# PV_PWM_heater_v2.net
KiCad netlist of a schematic drawn in Altium Designer
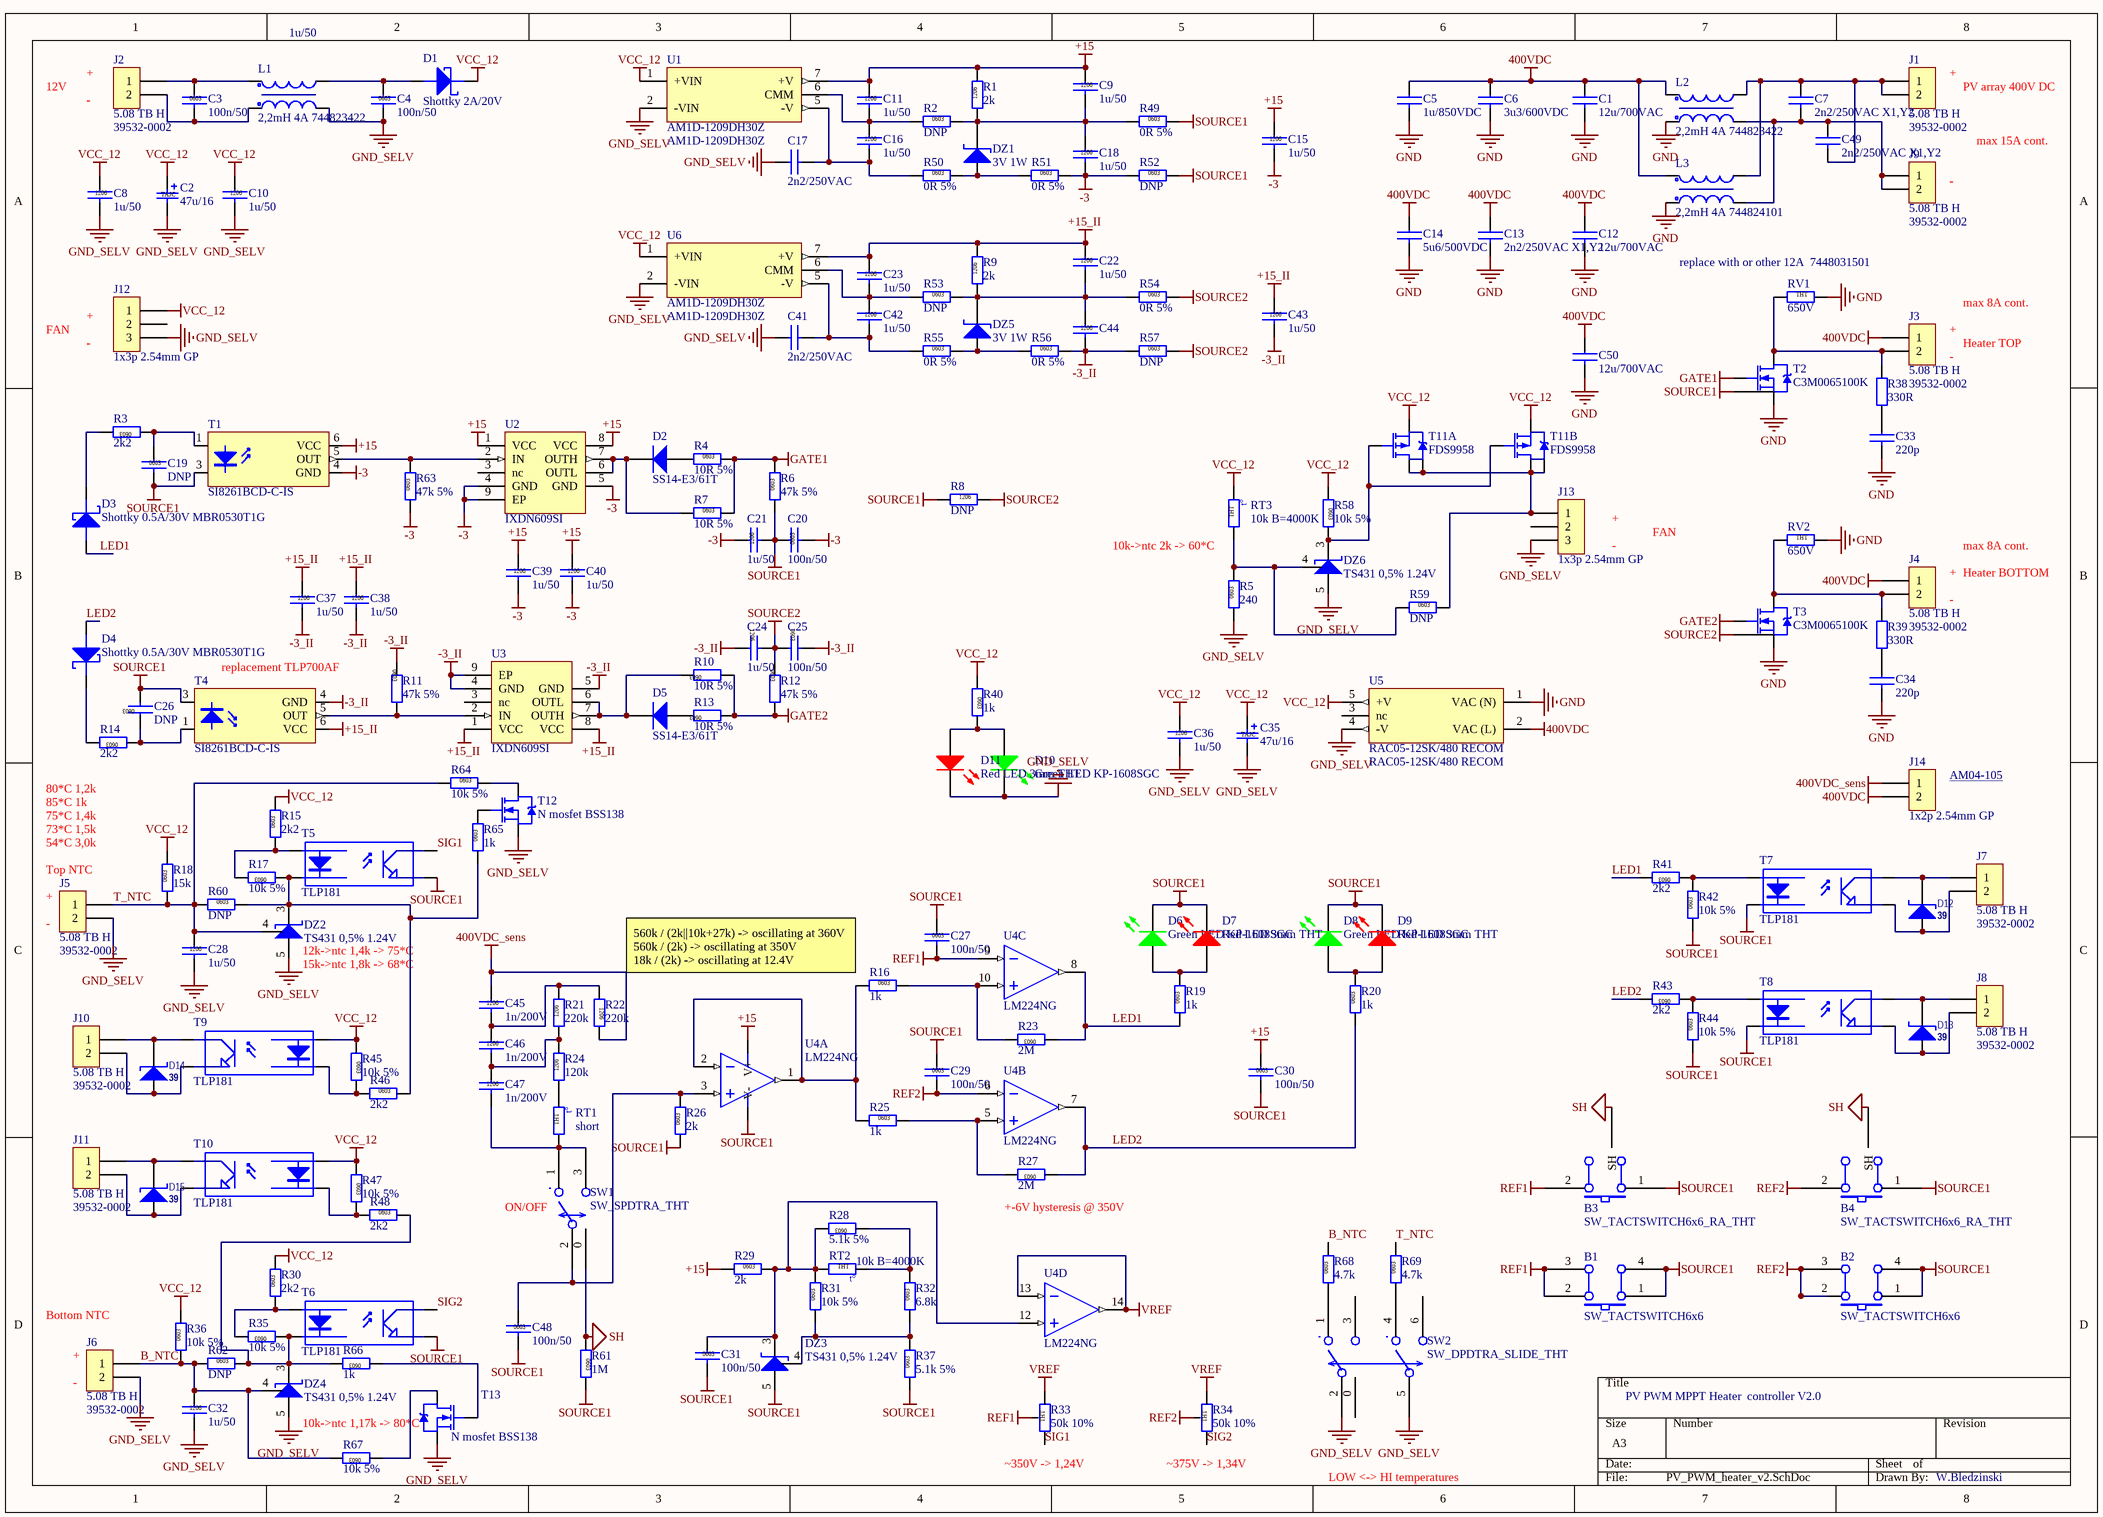
[diagram p0: PV_PWM_heater_v2.SchDoc]

(export (version "E")
  (design (tool "Eeschema 10.0.6"))
  (components
    (comp (ref "B1")
      (value "SW_TACTSWITCH6x6")
      (footprint "SW_TACT6x6")
      (description "SE PUSHBUTTON")
      (fields
        (field (name "MANUFACTURER") "ITT C&K")
        (field (name "MANUFACTURER PART NUMBER") "PTS645SK50SMTR92LFS")
      )
      (libsource (lib "WB") (part "SW_TACTSWITCH6x6"))
    )
    (comp (ref "B2")
      (value "SW_TACTSWITCH6x6")
      (footprint "SW_TACT6x6")
      (description "SE PUSHBUTTON")
      (fields
        (field (name "MANUFACTURER") "ITT C&K")
        (field (name "MANUFACTURER PART NUMBER") "PTS645SK50SMTR92LFS")
      )
      (libsource (lib "WB") (part "SW_TACTSWITCH6x6"))
    )
    (comp (ref "B3")
      (value "SW_TACTSWITCH6x6_RA_THT")
      (footprint "SW_TACT6x6_RA")
      (description "SE PUSHBUTTON")
      (fields (field (name "MANUFACTURER") "TE") (field (name "MANUFACTURER PART NUMBER") "1-1825027-1"))
      (libsource (lib "WB") (part "SW_TACTSWITCH6x6_RA_THT"))
    )
    (comp (ref "B4")
      (value "SW_TACTSWITCH6x6_RA_THT")
      (footprint "SW_TACT6x6_RA")
      (description "SE PUSHBUTTON")
      (fields (field (name "MANUFACTURER") "TE") (field (name "MANUFACTURER PART NUMBER") "1-1825027-1"))
      (libsource (lib "WB") (part "SW_TACTSWITCH6x6_RA_THT"))
    )
    (comp (ref "C1")
      (value "12u/700VAC")
      (footprint "CAP_THT27.5mm")
      (description "poliester capacitor THT")
      (fields
        (field (name "MANUFACTURER") "EPCOS")
        (field (name "MANUFACTURER PART NUMBER") "B32774D8126K000")
      )
      (libsource (lib "WB") (part "CAP_B_12u_700_THT"))
    )
    (comp (ref "C2")
      (value "47u/16")
      (footprint "TAJC")
      (description "ESR 1.2R 10VDC at 125stC")
      (fields
        (field (name "MANUFACTURER") "KEMET")
        (field (name "MANUFACTURER PART NUMBER") "T491C476K016AT")
      )
      (libsource (lib "WB") (part "CAP_E_47u_16_TAJC"))
    )
    (comp (ref "C3")
      (value "100n/50")
      (footprint "CAP_0603")
      (description "X7R chip capacitor")
      (fields
        (field (name "MANUFACTURER") "SAMSUNG")
        (field (name "MANUFACTURER PART NUMBER") "CL10B104KB8NNNC")
      )
      (libsource (lib "WB") (part "CAP_B_100n_50_0603_X7R"))
    )
    (comp (ref "C4")
      (value "100n/50")
      (footprint "CAP_0603")
      (description "X7R chip capacitor")
      (fields
        (field (name "MANUFACTURER") "SAMSUNG")
        (field (name "MANUFACTURER PART NUMBER") "CL10B104KB8NNNC")
      )
      (libsource (lib "WB") (part "CAP_B_100n_50_0603_X7R"))
    )
    (comp (ref "C5")
      (value "1u/850VDC")
      (footprint "CAP_AXIAL50X20mm")
      (description "poliester capacitor THT, esr 5mR, 9A/140A pk")
      (fields
        (field (name "MANUFACTURER") "KEMET")
        (field (name "MANUFACTURER PART NUMBER") "C4GAMUC4100AA1J")
      )
      (libsource (lib "WB") (part "CAP_B_1u_850_THT"))
    )
    (comp (ref "C6")
      (value "3u3/600VDC")
      (footprint "CAP_THT27.5X22mm")
      (description "poliester capacitor THT, esr 2.4mR, 25A/342A pk; 350VAC")
      (fields
        (field (name "MANUFACTURER") "KEMET")
        (field (name "MANUFACTURER PART NUMBER") "C4ATHBW4330A3GJ")
      )
      (libsource (lib "WB") (part "CAP_B_3u3_600_THT"))
    )
    (comp (ref "C7")
      (value "2n2/250VAC X1,Y2")
      (footprint "CAP_THT7.5mm")
      (description "poliester capacitor THT X1 Y2, Y5V")
      (fields (field (name "MANUFACTURER PART NUMBER") "CY2V-2N2") (field (name "TOLERANCE") "20%"))
      (libsource (lib "WB") (part "CAP_B_2n2_250_X1Y2_THT"))
    )
    (comp (ref "C8")
      (value "1u/50")
      (footprint "CAP_1206")
      (description "X7R chip capacitor")
      (fields
        (field (name "MANUFACTURER") "TDK")
        (field (name "MANUFACTURER PART NUMBER") "C3216X7R1H105K160AB")
      )
      (libsource (lib "WB") (part "CAP_B_1u_50_1206_X7R"))
    )
    (comp (ref "C9")
      (value "1u/50")
      (footprint "CAP_1206")
      (description "X7R chip capacitor")
      (fields
        (field (name "MANUFACTURER") "TDK")
        (field (name "MANUFACTURER PART NUMBER") "C3216X7R1H105K160AB")
      )
      (libsource (lib "WB") (part "CAP_B_1u_50_1206_X7R"))
    )
    (comp (ref "C10")
      (value "1u/50")
      (footprint "CAP_1206")
      (description "X7R chip capacitor")
      (fields
        (field (name "MANUFACTURER") "TDK")
        (field (name "MANUFACTURER PART NUMBER") "C3216X7R1H105K160AB")
      )
      (libsource (lib "WB") (part "CAP_B_1u_50_1206_X7R"))
    )
    (comp (ref "C11")
      (value "1u/50")
      (footprint "CAP_1206")
      (description "X7R chip capacitor")
      (fields
        (field (name "MANUFACTURER") "TDK")
        (field (name "MANUFACTURER PART NUMBER") "C3216X7R1H105K160AB")
      )
      (libsource (lib "WB") (part "CAP_B_1u_50_1206_X7R"))
    )
    (comp (ref "C12")
      (value "12u/700VAC")
      (footprint "CAP_THT27.5mm")
      (description "poliester capacitor THT")
      (fields
        (field (name "MANUFACTURER") "EPCOS")
        (field (name "MANUFACTURER PART NUMBER") "B32774D8126K000")
      )
      (libsource (lib "WB") (part "CAP_B_12u_700_THT"))
    )
    (comp (ref "C13")
      (value "2n2/250VAC X1,Y2")
      (footprint "CAP_THT7.5mm")
      (description "poliester capacitor THT X1 Y2, Y5V")
      (fields (field (name "MANUFACTURER PART NUMBER") "CY2V-2N2") (field (name "TOLERANCE") "20%"))
      (libsource (lib "WB") (part "CAP_B_2n2_250_X1Y2_THT"))
    )
    (comp (ref "C14")
      (value "5u6/500VDC")
      (footprint "CAP_THT27.5X11mm")
      (description "poliester capacitor THT, esr 13mR,")
      (fields (field (name "TOLERANCE") "10%") (field (name "VOLTAGE") "500VDC"))
      (libsource (lib "WB") (part "CAP_B_5u6_500_THT"))
    )
    (comp (ref "C15")
      (value "1u/50")
      (footprint "CAP_1206")
      (description "X7R chip capacitor")
      (fields
        (field (name "MANUFACTURER") "TDK")
        (field (name "MANUFACTURER PART NUMBER") "C3216X7R1H105K160AB")
      )
      (libsource (lib "WB") (part "CAP_B_1u_50_1206_X7R"))
    )
    (comp (ref "C16")
      (value "1u/50")
      (footprint "CAP_1206")
      (description "X7R chip capacitor")
      (fields
        (field (name "MANUFACTURER") "TDK")
        (field (name "MANUFACTURER PART NUMBER") "C3216X7R1H105K160AB")
      )
      (libsource (lib "WB") (part "CAP_B_1u_50_1206_X7R"))
    )
    (comp (ref "C17")
      (value "2n2/250VAC")
      (footprint "CAP_THT10mm")
      (description "poliester capacitor THT Y2")
      (fields
        (field (name "MANUFACTURER") "WIMA")
        (field (name "MANUFACTURER PART NUMBER") "MPY20W1220FA00MSSD")
      )
      (libsource (lib "WB") (part "CAP_B_2n2_250_THT"))
    )
    (comp (ref "C18")
      (value "1u/50")
      (footprint "CAP_1206")
      (description "X7R chip capacitor")
      (fields
        (field (name "MANUFACTURER") "TDK")
        (field (name "MANUFACTURER PART NUMBER") "C3216X7R1H105K160AB")
      )
      (libsource (lib "WB") (part "CAP_B_1u_50_1206_X7R"))
    )
    (comp (ref "C19")
      (value "DNP")
      (footprint "CAP_0603")
      (description "X7R chip capacitor")
      (fields
        (field (name "MANUFACTURER") "SAMSUNG")
        (field (name "MANUFACTURER PART NUMBER") "CL10B104KB8NNNC")
      )
      (libsource (lib "WB") (part "CAP_B_100n_50_0603_X7R"))
    )
    (comp (ref "C20")
      (value "100n/50")
      (footprint "CAP_0603")
      (description "X7R chip capacitor")
      (fields
        (field (name "MANUFACTURER") "SAMSUNG")
        (field (name "MANUFACTURER PART NUMBER") "CL10B104KB8NNNC")
      )
      (libsource (lib "WB") (part "CAP_B_100n_50_0603_X7R"))
    )
    (comp (ref "C21")
      (value "1u/50")
      (footprint "CAP_1206")
      (description "X7R chip capacitor")
      (fields
        (field (name "MANUFACTURER") "TDK")
        (field (name "MANUFACTURER PART NUMBER") "C3216X7R1H105K160AB")
      )
      (libsource (lib "WB") (part "CAP_B_1u_50_1206_X7R"))
    )
    (comp (ref "C22")
      (value "1u/50")
      (footprint "CAP_1206")
      (description "X7R chip capacitor")
      (fields
        (field (name "MANUFACTURER") "TDK")
        (field (name "MANUFACTURER PART NUMBER") "C3216X7R1H105K160AB")
      )
      (libsource (lib "WB") (part "CAP_B_1u_50_1206_X7R"))
    )
    (comp (ref "C23")
      (value "1u/50")
      (footprint "CAP_1206")
      (description "X7R chip capacitor")
      (fields
        (field (name "MANUFACTURER") "TDK")
        (field (name "MANUFACTURER PART NUMBER") "C3216X7R1H105K160AB")
      )
      (libsource (lib "WB") (part "CAP_B_1u_50_1206_X7R"))
    )
    (comp (ref "C24")
      (value "1u/50")
      (footprint "CAP_1206")
      (description "X7R chip capacitor")
      (fields
        (field (name "MANUFACTURER") "TDK")
        (field (name "MANUFACTURER PART NUMBER") "C3216X7R1H105K160AB")
      )
      (libsource (lib "WB") (part "CAP_B_1u_50_1206_X7R"))
    )
    (comp (ref "C25")
      (value "100n/50")
      (footprint "CAP_0603")
      (description "X7R chip capacitor")
      (fields
        (field (name "MANUFACTURER") "SAMSUNG")
        (field (name "MANUFACTURER PART NUMBER") "CL10B104KB8NNNC")
      )
      (libsource (lib "WB") (part "CAP_B_100n_50_0603_X7R"))
    )
    (comp (ref "C26")
      (value "DNP")
      (footprint "CAP_0603")
      (description "X7R chip capacitor")
      (fields
        (field (name "MANUFACTURER") "SAMSUNG")
        (field (name "MANUFACTURER PART NUMBER") "CL10B104KB8NNNC")
      )
      (libsource (lib "WB") (part "CAP_B_100n_50_0603_X7R"))
    )
    (comp (ref "C27")
      (value "100n/50")
      (footprint "CAP_0603")
      (description "X7R chip capacitor")
      (fields
        (field (name "MANUFACTURER") "SAMSUNG")
        (field (name "MANUFACTURER PART NUMBER") "CL10B104KB8NNNC")
      )
      (libsource (lib "WB") (part "CAP_B_100n_50_0603_X7R"))
    )
    (comp (ref "C28")
      (value "1u/50")
      (footprint "CAP_1206")
      (description "X7R chip capacitor")
      (fields
        (field (name "MANUFACTURER") "TDK")
        (field (name "MANUFACTURER PART NUMBER") "C3216X7R1H105K160AB")
      )
      (libsource (lib "WB") (part "CAP_B_1u_50_1206_X7R"))
    )
    (comp (ref "C29")
      (value "100n/50")
      (footprint "CAP_0603")
      (description "X7R chip capacitor")
      (fields
        (field (name "MANUFACTURER") "SAMSUNG")
        (field (name "MANUFACTURER PART NUMBER") "CL10B104KB8NNNC")
      )
      (libsource (lib "WB") (part "CAP_B_100n_50_0603_X7R"))
    )
    (comp (ref "C30")
      (value "100n/50")
      (footprint "CAP_0603")
      (description "X7R chip capacitor")
      (fields
        (field (name "MANUFACTURER") "SAMSUNG")
        (field (name "MANUFACTURER PART NUMBER") "CL10B104KB8NNNC")
      )
      (libsource (lib "WB") (part "CAP_B_100n_50_0603_X7R"))
    )
    (comp (ref "C31")
      (value "100n/50")
      (footprint "CAP_0603")
      (description "X7R chip capacitor")
      (fields
        (field (name "MANUFACTURER") "SAMSUNG")
        (field (name "MANUFACTURER PART NUMBER") "CL10B104KB8NNNC")
      )
      (libsource (lib "WB") (part "CAP_B_100n_50_0603_X7R"))
    )
    (comp (ref "C32")
      (value "1u/50")
      (footprint "CAP_1206")
      (description "X7R chip capacitor")
      (fields
        (field (name "MANUFACTURER") "TDK")
        (field (name "MANUFACTURER PART NUMBER") "C3216X7R1H105K160AB")
      )
      (libsource (lib "WB") (part "CAP_B_1u_50_1206_X7R"))
    )
    (comp (ref "C33")
      (value "220p")
      (footprint "CAP_THT7.5mm")
      (description "poliester capacitor THT X1 Y2, Y5V")
      (fields (field (name "MANUFACTURER PART NUMBER") "CY2V-2N2") (field (name "TOLERANCE") "20%"))
      (libsource (lib "WB") (part "CAP_B_2n2_250_X1Y2_THT"))
    )
    (comp (ref "C34")
      (value "220p")
      (footprint "CAP_THT7.5mm")
      (description "poliester capacitor THT X1 Y2, Y5V")
      (fields (field (name "MANUFACTURER PART NUMBER") "CY2V-2N2") (field (name "TOLERANCE") "20%"))
      (libsource (lib "WB") (part "CAP_B_2n2_250_X1Y2_THT"))
    )
    (comp (ref "C35")
      (value "47u/16")
      (footprint "TAJC")
      (description "ESR 1.2R 10VDC at 125stC")
      (fields
        (field (name "MANUFACTURER") "KEMET")
        (field (name "MANUFACTURER PART NUMBER") "T491C476K016AT")
      )
      (libsource (lib "WB") (part "CAP_E_47u_16_TAJC"))
    )
    (comp (ref "C36")
      (value "1u/50")
      (footprint "CAP_1206")
      (description "X7R chip capacitor")
      (fields
        (field (name "MANUFACTURER") "TDK")
        (field (name "MANUFACTURER PART NUMBER") "C3216X7R1H105K160AB")
      )
      (libsource (lib "WB") (part "CAP_B_1u_50_1206_X7R"))
    )
    (comp (ref "C37")
      (value "1u/50")
      (footprint "CAP_1206")
      (description "X7R chip capacitor")
      (fields
        (field (name "MANUFACTURER") "TDK")
        (field (name "MANUFACTURER PART NUMBER") "C3216X7R1H105K160AB")
      )
      (libsource (lib "WB") (part "CAP_B_1u_50_1206_X7R"))
    )
    (comp (ref "C38")
      (value "1u/50")
      (footprint "CAP_1206")
      (description "X7R chip capacitor")
      (fields
        (field (name "MANUFACTURER") "TDK")
        (field (name "MANUFACTURER PART NUMBER") "C3216X7R1H105K160AB")
      )
      (libsource (lib "WB") (part "CAP_B_1u_50_1206_X7R"))
    )
    (comp (ref "C39")
      (value "1u/50")
      (footprint "CAP_1206")
      (description "X7R chip capacitor")
      (fields
        (field (name "MANUFACTURER") "TDK")
        (field (name "MANUFACTURER PART NUMBER") "C3216X7R1H105K160AB")
      )
      (libsource (lib "WB") (part "CAP_B_1u_50_1206_X7R"))
    )
    (comp (ref "C40")
      (value "1u/50")
      (footprint "CAP_1206")
      (description "X7R chip capacitor")
      (fields
        (field (name "MANUFACTURER") "TDK")
        (field (name "MANUFACTURER PART NUMBER") "C3216X7R1H105K160AB")
      )
      (libsource (lib "WB") (part "CAP_B_1u_50_1206_X7R"))
    )
    (comp (ref "C41")
      (value "2n2/250VAC")
      (footprint "CAP_THT10mm")
      (description "poliester capacitor THT Y2")
      (fields
        (field (name "MANUFACTURER") "WIMA")
        (field (name "MANUFACTURER PART NUMBER") "MPY20W1220FA00MSSD")
      )
      (libsource (lib "WB") (part "CAP_B_2n2_250_THT"))
    )
    (comp (ref "C42")
      (value "1u/50")
      (footprint "CAP_1206")
      (description "X7R chip capacitor")
      (fields
        (field (name "MANUFACTURER") "TDK")
        (field (name "MANUFACTURER PART NUMBER") "C3216X7R1H105K160AB")
      )
      (libsource (lib "WB") (part "CAP_B_1u_50_1206_X7R"))
    )
    (comp (ref "C43")
      (value "1u/50")
      (footprint "CAP_1206")
      (description "X7R chip capacitor")
      (fields
        (field (name "MANUFACTURER") "TDK")
        (field (name "MANUFACTURER PART NUMBER") "C3216X7R1H105K160AB")
      )
      (libsource (lib "WB") (part "CAP_B_1u_50_1206_X7R"))
    )
    (comp (ref "C44")
      (value "1u/50")
      (footprint "CAP_1206")
      (description "X7R chip capacitor")
      (fields
        (field (name "MANUFACTURER") "TDK")
        (field (name "MANUFACTURER PART NUMBER") "C3216X7R1H105K160AB")
      )
      (libsource (lib "WB") (part "CAP_B_1u_50_1206_X7R"))
    )
    (comp (ref "C45")
      (value "1n/200V")
      (footprint "CAP_1206")
      (description "C0G chip capacitor")
      (fields
        (field (name "MANUFACTURER") "TDK")
        (field (name "MANUFACTURER PART NUMBER") "CGA5L2C0G1H104J160AA")
      )
      (libsource (lib "WB") (part "CAP_B_100n_50_1206_C0G"))
    )
    (comp (ref "C46")
      (value "1n/200V")
      (footprint "CAP_1206")
      (description "C0G chip capacitor")
      (fields
        (field (name "MANUFACTURER") "TDK")
        (field (name "MANUFACTURER PART NUMBER") "CGA5L2C0G1H104J160AA")
      )
      (libsource (lib "WB") (part "CAP_B_100n_50_1206_C0G"))
    )
    (comp (ref "C47")
      (value "1n/200V")
      (footprint "CAP_1206")
      (description "C0G chip capacitor")
      (fields
        (field (name "MANUFACTURER") "TDK")
        (field (name "MANUFACTURER PART NUMBER") "CGA5L2C0G1H104J160AA")
      )
      (libsource (lib "WB") (part "CAP_B_100n_50_1206_C0G"))
    )
    (comp (ref "C48")
      (value "100n/50")
      (footprint "CAP_0603")
      (description "X7R chip capacitor")
      (fields
        (field (name "MANUFACTURER") "SAMSUNG")
        (field (name "MANUFACTURER PART NUMBER") "CL10B104KB8NNNC")
      )
      (libsource (lib "WB") (part "CAP_B_100n_50_0603_X7R"))
    )
    (comp (ref "C49")
      (value "2n2/250VAC X1,Y2")
      (footprint "CAP_THT7.5mm")
      (description "poliester capacitor THT X1 Y2, Y5V")
      (fields (field (name "MANUFACTURER PART NUMBER") "CY2V-2N2") (field (name "TOLERANCE") "20%"))
      (libsource (lib "WB") (part "CAP_B_2n2_250_X1Y2_THT"))
    )
    (comp (ref "C50")
      (value "12u/700VAC")
      (footprint "CAP_THT27.5mm")
      (description "poliester capacitor THT")
      (fields
        (field (name "MANUFACTURER") "EPCOS")
        (field (name "MANUFACTURER PART NUMBER") "B32774D8126K000")
      )
      (libsource (lib "WB") (part "CAP_B_12u_700_THT"))
    )
    (comp (ref "D1")
      (value "Shottky 2A/20V")
      (footprint "SMA_DO-214AC")
      (description "Shottky Diode 0,5V @ 2A SMA 200pF")
      (fields (field (name "MANUFACTURER") "DIODES") (field (name "MANUFACTURER PART NUMBER") "B220A-13-F"))
      (libsource (lib "WB") (part "D_2A_20_B220A"))
    )
    (comp (ref "D2")
      (value "SS14-E3/61T")
      (footprint "SMA_DO-214AC")
      (fields (field (name "MANUFACTURER") "Vishay Semiconductors"))
      (libsource (lib "WB") (part "D_SS14"))
    )
    (comp (ref "D3")
      (value "Shottky 0.5A/30V MBR0530T1G")
      (footprint "SOD_123")
      (description "Shottky Diode trr 4ns 0,43V @ 0.5A 0.37V@0.1A")
      (fields (field (name "MANUFACTURER") "ON") (field (name "MANUFACTURER PART NUMBER") "MBR0530T1G"))
      (libsource (lib "WB") (part "D_0.5A_30_MBR0530T1G"))
    )
    (comp (ref "D4")
      (value "Shottky 0.5A/30V MBR0530T1G")
      (footprint "SOD_123")
      (description "Shottky Diode trr 4ns 0,43V @ 0.5A 0.37V@0.1A")
      (fields (field (name "MANUFACTURER") "ON") (field (name "MANUFACTURER PART NUMBER") "MBR0530T1G"))
      (libsource (lib "WB") (part "D_0.5A_30_MBR0530T1G"))
    )
    (comp (ref "D5")
      (value "SS14-E3/61T")
      (footprint "SMA_DO-214AC")
      (fields (field (name "MANUFACTURER") "Vishay Semiconductors"))
      (libsource (lib "WB") (part "D_SS14"))
    )
    (comp (ref "D6")
      (value "Green LED KP-1608SGC")
      (footprint "LED_0603_GREEN")
      (description "Diode LED SMD 2.2V @ 20mA 15mcd")
      (fields
        (field (name "MANUFACTURER") "KINGBRIGHT")
        (field (name "MANUFACTURER PART NUMBER") "KP-1608SGC")
      )
      (libsource (lib "WB") (part "D_LED_0603_GREEN"))
    )
    (comp (ref "D7")
      (value "Red LED 3mm THT")
      (footprint "LED_3MM")
      (description "Diode LED THT")
      (fields
        (field (name "MANUFACTURER") "KINGBRIGHT")
        (field (name "MANUFACTURER PART NUMBER") "L-934SRC-E")
      )
      (libsource (lib "WB") (part "D_LED3_THT_RED"))
    )
    (comp (ref "D8")
      (value "Green LED KP-1608SGC")
      (footprint "LED_0603_GREEN")
      (description "Diode LED SMD 2.2V @ 20mA 15mcd")
      (fields
        (field (name "MANUFACTURER") "KINGBRIGHT")
        (field (name "MANUFACTURER PART NUMBER") "KP-1608SGC")
      )
      (libsource (lib "WB") (part "D_LED_0603_GREEN"))
    )
    (comp (ref "D9")
      (value "Red LED 3mm THT")
      (footprint "LED_3MM")
      (description "Diode LED THT")
      (fields
        (field (name "MANUFACTURER") "KINGBRIGHT")
        (field (name "MANUFACTURER PART NUMBER") "L-934SRC-E")
      )
      (libsource (lib "WB") (part "D_LED3_THT_RED"))
    )
    (comp (ref "D10")
      (value "Green LED KP-1608SGC")
      (footprint "LED_0603_GREEN")
      (description "Diode LED SMD 2.2V @ 20mA 15mcd")
      (fields
        (field (name "MANUFACTURER") "KINGBRIGHT")
        (field (name "MANUFACTURER PART NUMBER") "KP-1608SGC")
      )
      (libsource (lib "WB") (part "D_LED_0603_GREEN"))
    )
    (comp (ref "D11")
      (value "Red LED 3mm THT")
      (footprint "LED_3MM")
      (description "Diode LED THT")
      (fields
        (field (name "MANUFACTURER") "KINGBRIGHT")
        (field (name "MANUFACTURER PART NUMBER") "L-934SRC-E")
      )
      (libsource (lib "WB") (part "D_LED3_THT_RED"))
    )
    (comp (ref "D12")
      (value "39")
      (footprint "SMA_DO-214AC")
      (description "transil jednostronny")
      (fields (field (name "MANUFACTURER") "STM") (field (name "MANUFACTURER PART NUMBER") "SMA6T39AY"))
      (libsource (lib "WB") (part "D_TR_UNI_SMA6TY_39V"))
    )
    (comp (ref "D13")
      (value "39")
      (footprint "SMA_DO-214AC")
      (description "transil jednostronny")
      (fields (field (name "MANUFACTURER") "STM") (field (name "MANUFACTURER PART NUMBER") "SMA6T39AY"))
      (libsource (lib "WB") (part "D_TR_UNI_SMA6TY_39V"))
    )
    (comp (ref "D14")
      (value "39")
      (footprint "SMA_DO-214AC")
      (description "transil jednostronny")
      (fields (field (name "MANUFACTURER") "STM") (field (name "MANUFACTURER PART NUMBER") "SMA6T39AY"))
      (libsource (lib "WB") (part "D_TR_UNI_SMA6TY_39V"))
    )
    (comp (ref "D15")
      (value "39")
      (footprint "SMA_DO-214AC")
      (description "transil jednostronny")
      (fields (field (name "MANUFACTURER") "STM") (field (name "MANUFACTURER PART NUMBER") "SMA6T39AY"))
      (libsource (lib "WB") (part "D_TR_UNI_SMA6TY_39V"))
    )
    (comp (ref "DZ1")
      (value "3V 1W")
      (footprint "D_DO-15_DO-204AC")
      (fields (field (name "VOLTAGE") "3"))
      (libsource (lib "WB") (part "D_1W_20_ZENER"))
    )
    (comp (ref "DZ2")
      (value "TS431 0,5% 1.24V")
      (footprint "SOT23_5_DBV_R-PDSO-G5")
      (description "0,5% 1.24V vref")
      (fields (field (name "VOLTAGE") "10V") (field (name "MANUFACTURER") "STMicroelectronics"))
      (libsource (lib "WB") (part "D_TS431BILT"))
    )
    (comp (ref "DZ3")
      (value "TS431 0,5% 1.24V")
      (footprint "SOT23_5_DBV_R-PDSO-G5")
      (description "0,5% 1.24V vref")
      (fields (field (name "VOLTAGE") "10V") (field (name "MANUFACTURER") "STMicroelectronics"))
      (libsource (lib "WB") (part "D_TS431BILT"))
    )
    (comp (ref "DZ4")
      (value "TS431 0,5% 1.24V")
      (footprint "SOT23_5_DBV_R-PDSO-G5")
      (description "0,5% 1.24V vref")
      (fields (field (name "VOLTAGE") "10V") (field (name "MANUFACTURER") "STMicroelectronics"))
      (libsource (lib "WB") (part "D_TS431BILT"))
    )
    (comp (ref "DZ5")
      (value "3V 1W")
      (footprint "D_DO-15_DO-204AC")
      (fields (field (name "VOLTAGE") "3"))
      (libsource (lib "WB") (part "D_1W_20_ZENER"))
    )
    (comp (ref "DZ6")
      (value "TS431 0,5% 1.24V")
      (footprint "SOT23_5_DBV_R-PDSO-G5")
      (description "0,5% 1.24V vref")
      (fields (field (name "VOLTAGE") "10V") (field (name "MANUFACTURER") "STMicroelectronics"))
      (libsource (lib "WB") (part "D_TS431BILT"))
    )
    (comp (ref "J1")
      (value "5.08 TB H")
      (footprint "CON_1x2_5.08TBRA")
      (description "THT 5,08mm, WE 691312510002, NINIGI TBG-5-KB-2P/GN, MLX 395320002")
      (fields (field (name "MANUFACTURER") "Molex") (field (name "MANUFACTURER PART NUMBER") "39532-0002"))
      (libsource (lib "") (part "CON_1x2_TB_5.08H_1"))
    )
    (comp (ref "J2")
      (value "5.08 TB H")
      (footprint "CON_1x2_5.08TBRA")
      (description "THT 5,08mm, WE 691312510002, NINIGI TBG-5-KB-2P/GN, MLX 395320002")
      (fields (field (name "MANUFACTURER") "Molex") (field (name "MANUFACTURER PART NUMBER") "39532-0002"))
      (libsource (lib "WB") (part "CON_1x2_TB_5.08H"))
    )
    (comp (ref "J3")
      (value "5.08 TB H")
      (footprint "CON_1x2_5.08TBRA")
      (description "THT 5,08mm, WE 691312510002, NINIGI TBG-5-KB-2P/GN, MLX 395320002")
      (fields (field (name "MANUFACTURER") "Molex") (field (name "MANUFACTURER PART NUMBER") "39532-0002"))
      (libsource (lib "") (part "CON_1x2_TB_5.08H_1"))
    )
    (comp (ref "J4")
      (value "5.08 TB H")
      (footprint "CON_1x2_5.08TBRA")
      (description "THT 5,08mm, WE 691312510002, NINIGI TBG-5-KB-2P/GN, MLX 395320002")
      (fields (field (name "MANUFACTURER") "Molex") (field (name "MANUFACTURER PART NUMBER") "39532-0002"))
      (libsource (lib "") (part "CON_1x2_TB_5.08H_1"))
    )
    (comp (ref "J5")
      (value "5.08 TB H")
      (footprint "CON_1x2_5.08TBRA")
      (description "THT 5,08mm, WE 691312510002, NINIGI TBG-5-KB-2P/GN, MLX 395320002")
      (fields (field (name "MANUFACTURER") "Molex") (field (name "MANUFACTURER PART NUMBER") "39532-0002"))
      (libsource (lib "WB") (part "CON_1x2_TB_5.08H"))
    )
    (comp (ref "J6")
      (value "5.08 TB H")
      (footprint "CON_1x2_5.08TBRA")
      (description "THT 5,08mm, WE 691312510002, NINIGI TBG-5-KB-2P/GN, MLX 395320002")
      (fields (field (name "MANUFACTURER") "Molex") (field (name "MANUFACTURER PART NUMBER") "39532-0002"))
      (libsource (lib "WB") (part "CON_1x2_TB_5.08H"))
    )
    (comp (ref "J7")
      (value "5.08 TB H")
      (footprint "CON_1x2_5.08TBRA")
      (description "THT 5,08mm, WE 691312510002, NINIGI TBG-5-KB-2P/GN, MLX 395320002")
      (fields (field (name "MANUFACTURER") "Molex") (field (name "MANUFACTURER PART NUMBER") "39532-0002"))
      (libsource (lib "") (part "CON_1x2_TB_5.08H_1"))
    )
    (comp (ref "J8")
      (value "5.08 TB H")
      (footprint "CON_1x2_5.08TBRA")
      (description "THT 5,08mm, WE 691312510002, NINIGI TBG-5-KB-2P/GN, MLX 395320002")
      (fields (field (name "MANUFACTURER") "Molex") (field (name "MANUFACTURER PART NUMBER") "39532-0002"))
      (libsource (lib "") (part "CON_1x2_TB_5.08H_1"))
    )
    (comp (ref "J9")
      (value "5.08 TB H")
      (footprint "CON_1x2_5.08TBRA")
      (description "THT 5,08mm, WE 691312510002, NINIGI TBG-5-KB-2P/GN, MLX 395320002")
      (fields (field (name "MANUFACTURER") "Molex") (field (name "MANUFACTURER PART NUMBER") "39532-0002"))
      (libsource (lib "") (part "CON_1x2_TB_5.08H_1"))
    )
    (comp (ref "J10")
      (value "5.08 TB H")
      (footprint "CON_1x2_5.08TBRA")
      (description "THT 5,08mm, WE 691312510002, NINIGI TBG-5-KB-2P/GN, MLX 395320002")
      (fields (field (name "MANUFACTURER") "Molex") (field (name "MANUFACTURER PART NUMBER") "39532-0002"))
      (libsource (lib "WB") (part "CON_1x2_TB_5.08H"))
    )
    (comp (ref "J11")
      (value "5.08 TB H")
      (footprint "CON_1x2_5.08TBRA")
      (description "THT 5,08mm, WE 691312510002, NINIGI TBG-5-KB-2P/GN, MLX 395320002")
      (fields (field (name "MANUFACTURER") "Molex") (field (name "MANUFACTURER PART NUMBER") "39532-0002"))
      (libsource (lib "WB") (part "CON_1x2_TB_5.08H"))
    )
    (comp (ref "J12")
      (value "1x3p 2.54mm GP")
      (footprint "CON_PIN1x3_THT")
      (description "THT 2,54 goldpin")
      (fields (field (name "MANUFACTURER") "TME") (field (name "MANUFACTURER PART NUMBER") "ZL201-03G"))
      (libsource (lib "") (part "CON_1x3_GP_THT_1"))
    )
    (comp (ref "J13")
      (value "1x3p 2.54mm GP")
      (footprint "CON_PIN1x3_THT")
      (description "THT 2,54 goldpin")
      (fields (field (name "MANUFACTURER") "TME") (field (name "MANUFACTURER PART NUMBER") "ZL201-03G"))
      (libsource (lib "WB") (part "CON_1x3_GP_THT"))
    )
    (comp (ref "J14")
      (value "1x2p 2.54mm GP")
      (footprint "CON_PIN1x2_THT")
      (description "THT 2,54 goldpin")
      (fields (field (name "MANUFACTURER") "TME") (field (name "MANUFACTURER PART NUMBER") "ZL201-02G"))
      (libsource (lib "WB") (part "CON_1x2_GP_THT"))
    )
    (comp (ref "L1")
      (value "2,2mH 4A 744823422")
      (footprint "IND_WE-CMB-M")
      (description "2x2,2mH 40dB 1MHz 4A 250VAC Rdc=2x0,03 SRF1MHz")
      (fields (field (name "MANUFACTURER") "WE") (field (name "MANUFACTURER PART NUMBER") "744823422"))
      (libsource (lib "WB") (part "IND_WE-CMB_2.2mH_4A_THT"))
    )
    (comp (ref "L2")
      (value "2,2mH 4A 744823422")
      (footprint "IND_WE-CMB-M")
      (description "2x2,2mH 40dB 1MHz 4A 250VAC Rdc=2x0,03 SRF1MHz")
      (fields (field (name "MANUFACTURER") "WE") (field (name "MANUFACTURER PART NUMBER") "744823422"))
      (libsource (lib "WB") (part "IND_WE-CMB_2.2mH_4A_THT"))
    )
    (comp (ref "L3")
      (value "2,2mH 4A 744824101")
      (footprint "IND_WE-CMB-l")
      (description "2x2,2mH 30dB 1MHz 10A 250VAC Rdc=2x0,007 SRF1MHz")
      (fields (field (name "MANUFACTURER") "WE") (field (name "MANUFACTURER PART NUMBER") "744824101"))
      (libsource (lib "WB") (part "IND_WE-CMB_2.2mH_10A_THT"))
    )
    (comp (ref "R1")
      (value "2k")
      (footprint "RES_1206")
      (description "Resistor 1206 5% 0,25W")
      (fields
        (field (name "MANUFACTURER") "YAGEO")
        (field (name "MANUFACTURER PART NUMBER") "RC1206JR-07510R")
      )
      (libsource (lib "") (part "RES_510R_5p_1206_1"))
    )
    (comp (ref "R2")
      (value "DNP")
      (footprint "RES_0603")
      (description "0603 ,1W")
      (fields
        (field (name "MANUFACTURER") "YAGEO")
        (field (name "MANUFACTURER PART NUMBER") "RC0603JR-070RL")
      )
      (libsource (lib "WB") (part "RES_0R_5p_0603"))
    )
    (comp (ref "R3")
      (value "2k2")
      (footprint "RES_0603")
      (description "Resistor 0603 5% 0,1W")
      (fields (field (name "MANUFACTURER") "YAGEO") (field (name "TOLERANCE") "5%"))
      (libsource (lib "") (part "RES_3k_5p_0603_2"))
    )
    (comp (ref "R4")
      (value "10R 5%")
      (footprint "RES_0603")
      (description "Resistor 0603 5% 0,1W")
      (fields (field (name "MANUFACTURER") "YAGEO") (field (name "TOLERANCE") "5%"))
      (libsource (lib "WB") (part "RES_10R_5p_0603"))
    )
    (comp (ref "R5")
      (value "240")
      (footprint "RES_0603")
      (description "Resistor 0603 5% 0,1W")
      (fields (field (name "MANUFACTURER") "YAGEO") (field (name "TOLERANCE") "5%"))
      (libsource (lib "") (part "RES_10R_5p_0603_1"))
    )
    (comp (ref "R6")
      (value "47k 5%")
      (footprint "RES_0603")
      (description "Resistor 0603 5% 0,1W")
      (fields (field (name "MANUFACTURER") "YAGEO") (field (name "TOLERANCE") "5%"))
      (libsource (lib "") (part "RES_47k_5p_0603_1"))
    )
    (comp (ref "R7")
      (value "10R 5%")
      (footprint "RES_0603")
      (description "Resistor 0603 5% 0,1W")
      (fields (field (name "MANUFACTURER") "YAGEO") (field (name "TOLERANCE") "5%"))
      (libsource (lib "WB") (part "RES_10R_5p_0603"))
    )
    (comp (ref "R8")
      (value "DNP")
      (footprint "RES_1206")
      (description "Resistor 1206 5% 0,25W")
      (fields
        (field (name "MANUFACTURER") "ROYAL OHM")
        (field (name "MANUFACTURER PART NUMBER") "1206S4J0000T5E")
      )
      (libsource (lib "WB") (part "RES_0R_5p_1206"))
    )
    (comp (ref "R9")
      (value "2k")
      (footprint "RES_1206")
      (description "Resistor 1206 5% 0,25W")
      (fields
        (field (name "MANUFACTURER") "YAGEO")
        (field (name "MANUFACTURER PART NUMBER") "RC1206JR-07510R")
      )
      (libsource (lib "") (part "RES_510R_5p_1206_1"))
    )
    (comp (ref "R10")
      (value "10R 5%")
      (footprint "RES_0603")
      (description "Resistor 0603 5% 0,1W")
      (fields (field (name "MANUFACTURER") "YAGEO") (field (name "TOLERANCE") "5%"))
      (libsource (lib "") (part "RES_10R_5p_0603_1"))
    )
    (comp (ref "R11")
      (value "47k 5%")
      (footprint "RES_0603")
      (description "Resistor 0603 5% 0,1W")
      (fields (field (name "MANUFACTURER") "YAGEO") (field (name "TOLERANCE") "5%"))
      (libsource (lib "WB") (part "RES_47k_5p_0603"))
    )
    (comp (ref "R12")
      (value "47k 5%")
      (footprint "RES_0603")
      (description "Resistor 0603 5% 0,1W")
      (fields (field (name "MANUFACTURER") "YAGEO") (field (name "TOLERANCE") "5%"))
      (libsource (lib "WB") (part "RES_47k_5p_0603"))
    )
    (comp (ref "R13")
      (value "10R 5%")
      (footprint "RES_0603")
      (description "Resistor 0603 5% 0,1W")
      (fields (field (name "MANUFACTURER") "YAGEO") (field (name "TOLERANCE") "5%"))
      (libsource (lib "") (part "RES_10R_5p_0603_1"))
    )
    (comp (ref "R14")
      (value "2k2")
      (footprint "RES_0603")
      (description "Resistor 0603 5% 0,1W")
      (fields (field (name "MANUFACTURER") "YAGEO") (field (name "TOLERANCE") "5%"))
      (libsource (lib "") (part "RES_3k_5p_0603_2"))
    )
    (comp (ref "R15")
      (value "2k2")
      (footprint "RES_0603")
      (description "Resistor 0603 5% 0,1W")
      (fields (field (name "MANUFACTURER") "YAGEO") (field (name "TOLERANCE") "5%"))
      (libsource (lib "") (part "RES_3k_5p_0603_1"))
    )
    (comp (ref "R16")
      (value "1k")
      (footprint "RES_0603")
      (description "Resistor 0603 5% 0,1W")
      (fields (field (name "MANUFACTURER") "YAGEO") (field (name "TOLERANCE") "5%"))
      (libsource (lib "WB") (part "RES_3k_5p_0603"))
    )
    (comp (ref "R17")
      (value "10k 5%")
      (footprint "RES_0603")
      (description "Resistor 0603 5% 0,1W")
      (fields (field (name "TOLERANCE") "5%") (field (name "VOLTAGE") "50"))
      (libsource (lib "") (part "RES_10k_5p_0603_2"))
    )
    (comp (ref "R18")
      (value "15k")
      (footprint "RES_0603")
      (description "Resistor 0603 5% 0,1W")
      (fields (field (name "TOLERANCE") "5%") (field (name "VOLTAGE") "50"))
      (libsource (lib "WB") (part "RES_10k_5p_0603"))
    )
    (comp (ref "R19")
      (value "1k")
      (footprint "RES_0603")
      (description "Resistor 0603 5% 0,1W")
      (fields (field (name "MANUFACTURER") "YAGEO") (field (name "TOLERANCE") "5%"))
      (libsource (lib "") (part "RES_3k_5p_0603_1"))
    )
    (comp (ref "R20")
      (value "1k")
      (footprint "RES_0603")
      (description "Resistor 0603 5% 0,1W")
      (fields (field (name "MANUFACTURER") "YAGEO") (field (name "TOLERANCE") "5%"))
      (libsource (lib "") (part "RES_3k_5p_0603_1"))
    )
    (comp (ref "R21")
      (value "220k")
      (footprint "RES_1206")
      (description "Resistor 1206 5% 0,25W")
      (fields
        (field (name "MANUFACTURER") "YAGEO")
        (field (name "MANUFACTURER PART NUMBER") "RC1206JR-07510R")
      )
      (libsource (lib "") (part "RES_510R_5p_1206_1"))
    )
    (comp (ref "R22")
      (value "220k")
      (footprint "RES_1206")
      (description "Resistor 1206 5% 0,25W")
      (fields
        (field (name "MANUFACTURER") "YAGEO")
        (field (name "MANUFACTURER PART NUMBER") "RC1206JR-07510R")
      )
      (libsource (lib "WB") (part "RES_510R_5p_1206"))
    )
    (comp (ref "R23")
      (value "2M")
      (footprint "RES_0603")
      (description "Resistor 0603 5% 0,1W")
      (fields (field (name "MANUFACTURER") "YAGEO") (field (name "TOLERANCE") "5%"))
      (libsource (lib "") (part "RES_3k_5p_0603_2"))
    )
    (comp (ref "R24")
      (value "120k")
      (footprint "RES_1206")
      (description "Resistor 1206 5% 0,25W")
      (fields
        (field (name "MANUFACTURER") "YAGEO")
        (field (name "MANUFACTURER PART NUMBER") "RC1206JR-07510R")
      )
      (libsource (lib "") (part "RES_510R_5p_1206_1"))
    )
    (comp (ref "R25")
      (value "1k")
      (footprint "RES_0603")
      (description "Resistor 0603 5% 0,1W")
      (fields (field (name "MANUFACTURER") "YAGEO") (field (name "TOLERANCE") "5%"))
      (libsource (lib "WB") (part "RES_3k_5p_0603"))
    )
    (comp (ref "R26")
      (value "2k")
      (footprint "RES_0603")
      (description "Resistor 0603 5% 0,1W")
      (fields (field (name "MANUFACTURER") "YAGEO") (field (name "TOLERANCE") "5%"))
      (libsource (lib "") (part "RES_3k_5p_0603_1"))
    )
    (comp (ref "R27")
      (value "2M")
      (footprint "RES_0603")
      (description "Resistor 0603 5% 0,1W")
      (fields (field (name "MANUFACTURER") "YAGEO") (field (name "TOLERANCE") "5%"))
      (libsource (lib "") (part "RES_3k_5p_0603_2"))
    )
    (comp (ref "R28")
      (value "5.1k 5%")
      (footprint "RES_0603")
      (description "Resistor 0603 5% 0,1W")
      (fields (field (name "TOLERANCE") "5%") (field (name "VOLTAGE") "50"))
      (libsource (lib "") (part "RES_5.1k_5p_0603_1"))
    )
    (comp (ref "R29")
      (value "2k")
      (footprint "RES_0603")
      (description "Resistor 0603 5% 0,1W")
      (fields (field (name "MANUFACTURER") "YAGEO") (field (name "TOLERANCE") "5%"))
      (libsource (lib "WB") (part "RES_3k_5p_0603"))
    )
    (comp (ref "R30")
      (value "2k2")
      (footprint "RES_0603")
      (description "Resistor 0603 5% 0,1W")
      (fields (field (name "MANUFACTURER") "YAGEO") (field (name "TOLERANCE") "5%"))
      (libsource (lib "") (part "RES_3k_5p_0603_1"))
    )
    (comp (ref "R31")
      (value "10k 5%")
      (footprint "RES_0603")
      (description "Resistor 0603 5% 0,1W")
      (fields (field (name "TOLERANCE") "5%") (field (name "VOLTAGE") "50"))
      (libsource (lib "WB") (part "RES_10k_5p_0603"))
    )
    (comp (ref "R32")
      (value "6.8k")
      (footprint "RES_0603")
      (description "Resistor 0603 5% 0,1W")
      (fields (field (name "TOLERANCE") "5%") (field (name "VOLTAGE") "50"))
      (libsource (lib "WB") (part "RES_10k_5p_0603"))
    )
    (comp (ref "R33")
      (value "50k 10%")
      (footprint "RES_PV36")
      (description "Pot 500mW wieloobrotowy")
      (fields
        (field (name "MANUFACTURER") "SR PASSIVES")
        (field (name "MANUFACTURER PART NUMBER") "T910W-50K")
      )
      (libsource (lib "WB") (part "RESV_50k_10p_THT"))
    )
    (comp (ref "R34")
      (value "50k 10%")
      (footprint "RES_PV36")
      (description "Pot 500mW wieloobrotowy")
      (fields
        (field (name "MANUFACTURER") "SR PASSIVES")
        (field (name "MANUFACTURER PART NUMBER") "T910W-50K")
      )
      (libsource (lib "WB") (part "RESV_50k_10p_THT"))
    )
    (comp (ref "R35")
      (value "10k 5%")
      (footprint "RES_0603")
      (description "Resistor 0603 5% 0,1W")
      (fields (field (name "TOLERANCE") "5%") (field (name "VOLTAGE") "50"))
      (libsource (lib "") (part "RES_10k_5p_0603_2"))
    )
    (comp (ref "R36")
      (value "10k 5%")
      (footprint "RES_0603")
      (description "Resistor 0603 5% 0,1W")
      (fields (field (name "TOLERANCE") "5%") (field (name "VOLTAGE") "50"))
      (libsource (lib "WB") (part "RES_10k_5p_0603"))
    )
    (comp (ref "R37")
      (value "5.1k 5%")
      (footprint "RES_0603")
      (description "Resistor 0603 5% 0,1W")
      (fields (field (name "TOLERANCE") "5%") (field (name "VOLTAGE") "50"))
      (libsource (lib "WB") (part "RES_5.1k_5p_0603"))
    )
    (comp (ref "R38")
      (value "330R")
      (footprint "RES_AXIAL2W")
      (description "Resistor 2W 5% THT")
      (fields (field (name "TOLERANCE") "5%"))
      (libsource (lib "WB") (part "RES_330R_5p_2W"))
    )
    (comp (ref "R39")
      (value "330R")
      (footprint "RES_AXIAL2W")
      (description "Resistor 2W 5% THT")
      (fields (field (name "TOLERANCE") "5%"))
      (libsource (lib "WB") (part "RES_330R_5p_2W"))
    )
    (comp (ref "R40")
      (value "1k")
      (footprint "RES_0603")
      (description "Resistor 0603 5% 0,1W")
      (fields (field (name "MANUFACTURER") "YAGEO") (field (name "TOLERANCE") "5%"))
      (libsource (lib "") (part "RES_3k_5p_0603_3"))
    )
    (comp (ref "R41")
      (value "2k2")
      (footprint "RES_0603")
      (description "Resistor 0603 5% 0,1W")
      (fields (field (name "MANUFACTURER") "YAGEO") (field (name "TOLERANCE") "5%"))
      (libsource (lib "") (part "RES_3k_5p_0603_2"))
    )
    (comp (ref "R42")
      (value "10k 5%")
      (footprint "RES_0603")
      (description "Resistor 0603 5% 0,1W")
      (fields (field (name "TOLERANCE") "5%") (field (name "VOLTAGE") "50"))
      (libsource (lib "WB") (part "RES_10k_5p_0603"))
    )
    (comp (ref "R43")
      (value "2k2")
      (footprint "RES_0603")
      (description "Resistor 0603 5% 0,1W")
      (fields (field (name "MANUFACTURER") "YAGEO") (field (name "TOLERANCE") "5%"))
      (libsource (lib "") (part "RES_3k_5p_0603_2"))
    )
    (comp (ref "R44")
      (value "10k 5%")
      (footprint "RES_0603")
      (description "Resistor 0603 5% 0,1W")
      (fields (field (name "TOLERANCE") "5%") (field (name "VOLTAGE") "50"))
      (libsource (lib "WB") (part "RES_10k_5p_0603"))
    )
    (comp (ref "R45")
      (value "10k 5%")
      (footprint "RES_0603")
      (description "Resistor 0603 5% 0,1W")
      (fields (field (name "TOLERANCE") "5%") (field (name "VOLTAGE") "50"))
      (libsource (lib "") (part "RES_10k_5p_0603_1"))
    )
    (comp (ref "R46")
      (value "2k2")
      (footprint "RES_0603")
      (description "Resistor 0603 5% 0,1W")
      (fields (field (name "MANUFACTURER") "YAGEO") (field (name "TOLERANCE") "5%"))
      (libsource (lib "WB") (part "RES_3k_5p_0603"))
    )
    (comp (ref "R47")
      (value "10k 5%")
      (footprint "RES_0603")
      (description "Resistor 0603 5% 0,1W")
      (fields (field (name "TOLERANCE") "5%") (field (name "VOLTAGE") "50"))
      (libsource (lib "") (part "RES_10k_5p_0603_1"))
    )
    (comp (ref "R48")
      (value "2k2")
      (footprint "RES_0603")
      (description "Resistor 0603 5% 0,1W")
      (fields (field (name "MANUFACTURER") "YAGEO") (field (name "TOLERANCE") "5%"))
      (libsource (lib "WB") (part "RES_3k_5p_0603"))
    )
    (comp (ref "R49")
      (value "0R 5%")
      (footprint "RES_0603")
      (description "0603 ,1W")
      (fields
        (field (name "MANUFACTURER") "YAGEO")
        (field (name "MANUFACTURER PART NUMBER") "RC0603JR-070RL")
      )
      (libsource (lib "WB") (part "RES_0R_5p_0603"))
    )
    (comp (ref "R50")
      (value "0R 5%")
      (footprint "RES_0603")
      (description "0603 ,1W")
      (fields
        (field (name "MANUFACTURER") "YAGEO")
        (field (name "MANUFACTURER PART NUMBER") "RC0603JR-070RL")
      )
      (libsource (lib "WB") (part "RES_0R_5p_0603"))
    )
    (comp (ref "R51")
      (value "0R 5%")
      (footprint "RES_0603")
      (description "0603 ,1W")
      (fields
        (field (name "MANUFACTURER") "YAGEO")
        (field (name "MANUFACTURER PART NUMBER") "RC0603JR-070RL")
      )
      (libsource (lib "WB") (part "RES_0R_5p_0603"))
    )
    (comp (ref "R52")
      (value "DNP")
      (footprint "RES_0603")
      (description "0603 ,1W")
      (fields
        (field (name "MANUFACTURER") "YAGEO")
        (field (name "MANUFACTURER PART NUMBER") "RC0603JR-070RL")
      )
      (libsource (lib "WB") (part "RES_0R_5p_0603"))
    )
    (comp (ref "R53")
      (value "DNP")
      (footprint "RES_0603")
      (description "0603 ,1W")
      (fields
        (field (name "MANUFACTURER") "YAGEO")
        (field (name "MANUFACTURER PART NUMBER") "RC0603JR-070RL")
      )
      (libsource (lib "WB") (part "RES_0R_5p_0603"))
    )
    (comp (ref "R54")
      (value "0R 5%")
      (footprint "RES_0603")
      (description "0603 ,1W")
      (fields
        (field (name "MANUFACTURER") "YAGEO")
        (field (name "MANUFACTURER PART NUMBER") "RC0603JR-070RL")
      )
      (libsource (lib "WB") (part "RES_0R_5p_0603"))
    )
    (comp (ref "R55")
      (value "0R 5%")
      (footprint "RES_0603")
      (description "0603 ,1W")
      (fields
        (field (name "MANUFACTURER") "YAGEO")
        (field (name "MANUFACTURER PART NUMBER") "RC0603JR-070RL")
      )
      (libsource (lib "WB") (part "RES_0R_5p_0603"))
    )
    (comp (ref "R56")
      (value "0R 5%")
      (footprint "RES_0603")
      (description "0603 ,1W")
      (fields
        (field (name "MANUFACTURER") "YAGEO")
        (field (name "MANUFACTURER PART NUMBER") "RC0603JR-070RL")
      )
      (libsource (lib "WB") (part "RES_0R_5p_0603"))
    )
    (comp (ref "R57")
      (value "DNP")
      (footprint "RES_0603")
      (description "0603 ,1W")
      (fields
        (field (name "MANUFACTURER") "YAGEO")
        (field (name "MANUFACTURER PART NUMBER") "RC0603JR-070RL")
      )
      (libsource (lib "WB") (part "RES_0R_5p_0603"))
    )
    (comp (ref "R58")
      (value "10k 5%")
      (footprint "RES_0603")
      (description "Resistor 0603 5% 0,1W")
      (fields (field (name "TOLERANCE") "5%") (field (name "VOLTAGE") "50"))
      (libsource (lib "") (part "RES_10k_5p_0603_1"))
    )
    (comp (ref "R59")
      (value "DNP")
      (footprint "RES_0603")
      (description "Resistor 0603 5% 0,1W")
      (fields (field (name "MANUFACTURER") "YAGEO") (field (name "TOLERANCE") "5%"))
      (libsource (lib "WB") (part "RES_3k_5p_0603"))
    )
    (comp (ref "R60")
      (value "DNP")
      (footprint "RES_0603")
      (description "Resistor 0603 5% 0,1W")
      (fields (field (name "MANUFACTURER") "YAGEO") (field (name "TOLERANCE") "5%"))
      (libsource (lib "WB") (part "RES_3k_5p_0603"))
    )
    (comp (ref "R61")
      (value "1M")
      (footprint "RES_0603")
      (description "Resistor 0603 5% 0,1W")
      (fields (field (name "MANUFACTURER") "YAGEO") (field (name "TOLERANCE") "5%"))
      (libsource (lib "") (part "RES_3k_5p_0603_3"))
    )
    (comp (ref "R62")
      (value "DNP")
      (footprint "RES_0603")
      (description "Resistor 0603 5% 0,1W")
      (fields (field (name "MANUFACTURER") "YAGEO") (field (name "TOLERANCE") "5%"))
      (libsource (lib "WB") (part "RES_3k_5p_0603"))
    )
    (comp (ref "R63")
      (value "47k 5%")
      (footprint "RES_0603")
      (description "Resistor 0603 5% 0,1W")
      (fields (field (name "MANUFACTURER") "YAGEO") (field (name "TOLERANCE") "5%"))
      (libsource (lib "") (part "RES_47k_5p_0603_1"))
    )
    (comp (ref "R64")
      (value "10k 5%")
      (footprint "RES_0603")
      (description "Resistor 0603 5% 0,1W")
      (fields (field (name "TOLERANCE") "5%") (field (name "VOLTAGE") "50"))
      (libsource (lib "") (part "RES_10k_5p_0603_3"))
    )
    (comp (ref "R65")
      (value "1k")
      (footprint "RES_0603")
      (description "Resistor 0603 5% 0,1W")
      (fields (field (name "MANUFACTURER") "YAGEO") (field (name "TOLERANCE") "5%"))
      (libsource (lib "") (part "RES_3k_5p_0603_1"))
    )
    (comp (ref "R66")
      (value "1k")
      (footprint "RES_0603")
      (description "Resistor 0603 5% 0,1W")
      (fields (field (name "MANUFACTURER") "YAGEO") (field (name "TOLERANCE") "5%"))
      (libsource (lib "") (part "RES_3k_5p_0603_2"))
    )
    (comp (ref "R67")
      (value "10k 5%")
      (footprint "RES_0603")
      (description "Resistor 0603 5% 0,1W")
      (fields (field (name "TOLERANCE") "5%") (field (name "VOLTAGE") "50"))
      (libsource (lib "") (part "RES_10k_5p_0603_2"))
    )
    (comp (ref "R68")
      (value "4.7k")
      (footprint "RES_0603")
      (description "Resistor 0603 5% 0,1W")
      (fields (field (name "TOLERANCE") "5%") (field (name "VOLTAGE") "50"))
      (libsource (lib "WB") (part "RES_10k_5p_0603"))
    )
    (comp (ref "R69")
      (value "4.7k")
      (footprint "RES_0603")
      (description "Resistor 0603 5% 0,1W")
      (fields (field (name "TOLERANCE") "5%") (field (name "VOLTAGE") "50"))
      (libsource (lib "WB") (part "RES_10k_5p_0603"))
    )
    (comp (ref "RT1")
      (value "short")
      (footprint "CON_PIN1x2_THT")
      (description "TERMISTOR, NTC, 4000K fi 6,5mm")
      (fields
        (field (name "MANUFACTURER") "SR PASSIVES")
        (field (name "MANUFACTURER PART NUMBER") "NTCC-10K")
      )
      (libsource (lib "WB") (part "REST_10k_10p_THT"))
    )
    (comp (ref "RT2")
      (value "10k B=4000K")
      (footprint "CON_PIN1x2_THT")
      (description "TERMISTOR, NTC, 4000K fi 6,5mm")
      (fields
        (field (name "MANUFACTURER") "SR PASSIVES")
        (field (name "MANUFACTURER PART NUMBER") "NTCC-10K")
      )
      (libsource (lib "") (part "REST_10k_10p_THT_1"))
    )
    (comp (ref "RT3")
      (value "10k B=4000K")
      (footprint "CON_PIN1x2_THT")
      (description "TERMISTOR, NTC, 4000K fi 6,5mm")
      (fields
        (field (name "MANUFACTURER") "SR PASSIVES")
        (field (name "MANUFACTURER PART NUMBER") "NTCC-10K")
      )
      (libsource (lib "WB") (part "REST_10k_10p_THT"))
    )
    (comp (ref "RV1")
      (value "650V")
      (footprint "RES_VAR_S14")
      (description "warystor S14 30VAC 38VDC 1kA 9J@2ms")
      (fields
        (field (name "MANUFACTURER") "EPCOS")
        (field (name "MANUFACTURER PART NUMBER") "B72214S0300K101")
      )
      (libsource (lib "WB") (part "RESV_38V_1kA_THT"))
    )
    (comp (ref "RV2")
      (value "650V")
      (footprint "RES_VAR_S14")
      (description "warystor S14 30VAC 38VDC 1kA 9J@2ms")
      (fields
        (field (name "MANUFACTURER") "EPCOS")
        (field (name "MANUFACTURER PART NUMBER") "B72214S0300K101")
      )
      (libsource (lib "WB") (part "RESV_38V_1kA_THT"))
    )
    (comp (ref "SW1")
      (value "SW_SPDTRA_THT")
      (footprint "SW_SPDT_RA")
      (libsource (lib "WB") (part "SW_SPDTRA_THT"))
    )
    (comp (ref "SW2")
      (value "SW_DPDTRA_SLIDE_THT")
      (footprint "SW_DPDT_SLIDE")
      (fields (field (name "MANUFACTURER PART NUMBER") "SK22d02"))
      (libsource (lib "WB") (part "SW_DPDTRA_SLIDE_THT"))
    )
    (comp (ref "T1")
      (value "SI8261BCD-C-IS")
      (footprint "SDPI6_SOICW6")
      (description "4.0 A ISOLATED GATE DRIVER 5kV Vdd6.5-30V")
      (fields (field (name "MANUFACTURER") "SiLabs"))
      (libsource (lib "WB") (part "T_SI8261"))
    )
    (comp (ref "T2")
      (value "C3M0065100K")
      (footprint "TO247-4")
      (description "SiC 1kV 35A N mosfet Rdson 0.07@UGS=15V Qg=35nC")
      (fields (field (name "MANUFACTURER") "CREE/wolfspeed") (field (name "VOLTAGE") "1kV"))
      (libsource (lib "WB") (part "T_C3M0065100K_THT"))
    )
    (comp (ref "T3")
      (value "C3M0065100K")
      (footprint "TO247-4")
      (description "SiC 1kV 35A N mosfet Rdson 0.07@UGS=15V Qg=35nC")
      (fields (field (name "MANUFACTURER") "CREE/wolfspeed") (field (name "VOLTAGE") "1kV"))
      (libsource (lib "WB") (part "T_C3M0065100K_THT"))
    )
    (comp (ref "T4")
      (value "SI8261BCD-C-IS")
      (footprint "SDPI6_SOICW6")
      (description "4.0 A ISOLATED GATE DRIVER 5kV Vdd6.5-30V")
      (fields (field (name "MANUFACTURER") "SiLabs"))
      (libsource (lib "") (part "T_SI8261_1"))
    )
    (comp (ref "T5") (value "TLP181") (footprint "TOSH-11-4C1_N") (libsource (lib "WB") (part "T_TLP181")))
    (comp (ref "T6") (value "TLP181") (footprint "TOSH-11-4C1_N") (libsource (lib "WB") (part "T_TLP181")))
    (comp (ref "T7") (value "TLP181") (footprint "TOSH-11-4C1_N") (libsource (lib "WB") (part "T_TLP181")))
    (comp (ref "T8") (value "TLP181") (footprint "TOSH-11-4C1_N") (libsource (lib "WB") (part "T_TLP181")))
    (comp (ref "T9") (value "TLP181") (footprint "TOSH-11-4C1_N") (libsource (lib "WB") (part "T_TLP181")))
    (comp (ref "T10") (value "TLP181") (footprint "TOSH-11-4C1_N") (libsource (lib "WB") (part "T_TLP181")))
    (comp (ref "T11")
      (value "~")
      (footprint "SOIC8M")
      (description "-60V -2.9A 2x P MOSFET, 135/105mR")
      (fields
        (field (name "MANUFACTURER") "ON Semiconductor / Fairchild")
        (field (name "MANUFACTURER PART NUMBER") "FDS9958")
      )
      (libsource (lib "WB") (part "T_FDS9958"))
    )
    (comp (ref "T12")
      (value "N mosfet BSS138")
      (footprint "SOT23-3")
      (description "50V 0.3A N mosfet Rdson 6ohm @UGS=4.5V Qg=2.5nC")
      (fields (field (name "MANUFACTURER") "FAIRCHILD") (field (name "MANUFACTURER PART NUMBER") "BSS138"))
      (libsource (lib "WB") (part "T_BSS138"))
    )
    (comp (ref "T13")
      (value "N mosfet BSS138")
      (footprint "SOT23-3")
      (description "50V 0.3A N mosfet Rdson 6ohm @UGS=4.5V Qg=2.5nC")
      (fields (field (name "MANUFACTURER") "FAIRCHILD") (field (name "MANUFACTURER PART NUMBER") "BSS138"))
      (libsource (lib "WB") (part "T_BSS138"))
    )
    (comp (ref "U1")
      (value "AM1D-1209DH30Z")
      (footprint "MOD_AIMTEC_AM1D-Z")
      (description "SMPS converter +9V and -9V, 1W, 3kV iso")
      (fields
        (field (name "MANUFACTURER") "AIMTEC")
        (field (name "VOLTAGE") "9, -9V")
        (field (name "MANUFACTURER PART NUMBER") "AM1D-1209DH30Z")
      )
      (libsource (lib "WB") (part "MOD_AM1D-1209DH30Z_THT"))
    )
    (comp (ref "U2")
      (value "IXDN609SI")
      (footprint "SOIC8M_PP")
      (description "single 9A High-speed low side gate driver")
      (fields (field (name "MANUFACTURER") "IXYS"))
      (libsource (lib "WB") (part "IC_IXDN609SI"))
    )
    (comp (ref "U3")
      (value "IXDN609SI")
      (footprint "SOIC8M_PP")
      (description "single 9A High-speed low side gate driver")
      (fields (field (name "MANUFACTURER") "IXYS"))
      (libsource (lib "") (part "IC_IXDN609SI_1"))
    )
    (comp (ref "U4")
      (value "LM224NG")
      (footprint "DIP14")
      (description "LM224_324_2902_NCV2902-14")
      (fields (field (name "MANUFACTURER") "ON SEMICONDUCTOR"))
      (libsource (lib "WB") (part "IC_LM224"))
    )
    (comp (ref "U5")
      (value "RAC05-12SK/480 RECOM")
      (footprint "MOD_RAC10-12SK/277")
      (description "SMPS 10W 12V 800mA, 430V DC in")
      (fields
        (field (name "MANUFACTURER") "RECOM")
        (field (name "VOLTAGE") "430V to 12V DC")
        (field (name "MANUFACTURER PART NUMBER") "RAC05-12SK/480 RECOM")
      )
      (libsource (lib "WB") (part "MOD_RAC10-12SK/277_THT"))
    )
    (comp (ref "U6")
      (value "AM1D-1209DH30Z")
      (footprint "MOD_AIMTEC_AM1D-Z")
      (description "SMPS converter +9V and -9V, 1W, 3kV iso")
      (fields
        (field (name "MANUFACTURER") "AIMTEC")
        (field (name "VOLTAGE") "9, -9V")
        (field (name "MANUFACTURER PART NUMBER") "AM1D-1209DH30Z")
      )
      (libsource (lib "WB") (part "MOD_AM1D-1209DH30Z_THT"))
    )
  )
  (nets
    (net (code "1") (name "+15") (class "Default")
      (node (ref "C11") (pin "1") (pinfunction "1_1") (pintype "passive"))
      (node (ref "C15") (pin "1") (pinfunction "1_1") (pintype "passive"))
      (node (ref "C30") (pin "1") (pinfunction "1_1") (pintype "passive"))
      (node (ref "C39") (pin "1") (pinfunction "1_1") (pintype "passive"))
      (node (ref "C40") (pin "1") (pinfunction "1_1") (pintype "passive"))
      (node (ref "C9") (pin "1") (pinfunction "1_1") (pintype "passive"))
      (node (ref "R1") (pin "2") (pinfunction "2_2") (pintype "passive"))
      (node (ref "R29") (pin "1") (pinfunction "1_1") (pintype "passive"))
      (node (ref "T1") (pin "6") (pinfunction "VCC_6") (pintype "power_in"))
      (node (ref "U1") (pin "7") (pinfunction "+V_7") (pintype "output"))
      (node (ref "U2") (pin "1") (pinfunction "VCC_1") (pintype "power_in"))
      (node (ref "U2") (pin "8") (pinfunction "VCC_8") (pintype "power_in"))
      (node (ref "U4") (pin "4") (pinfunction "V+_4") (pintype "power_in"))
    )
    (net (code "2") (name "+15_II") (class "Default")
      (node (ref "C22") (pin "1") (pinfunction "1_1") (pintype "passive"))
      (node (ref "C23") (pin "1") (pinfunction "1_1") (pintype "passive"))
      (node (ref "C37") (pin "1") (pinfunction "1_1") (pintype "passive"))
      (node (ref "C38") (pin "1") (pinfunction "1_1") (pintype "passive"))
      (node (ref "C43") (pin "1") (pinfunction "1_1") (pintype "passive"))
      (node (ref "R9") (pin "2") (pinfunction "2_2") (pintype "passive"))
      (node (ref "T4") (pin "6") (pinfunction "VCC_6") (pintype "power_in"))
      (node (ref "U3") (pin "1") (pinfunction "VCC_1") (pintype "power_in"))
      (node (ref "U3") (pin "8") (pinfunction "VCC_8") (pintype "power_in"))
      (node (ref "U6") (pin "7") (pinfunction "+V_7") (pintype "output"))
    )
    (net (code "3") (name "-3") (class "Default")
      (node (ref "C15") (pin "2") (pinfunction "2_2") (pintype "passive"))
      (node (ref "C18") (pin "2") (pinfunction "2_2") (pintype "passive"))
      (node (ref "C20") (pin "2") (pinfunction "2_2") (pintype "passive"))
      (node (ref "C21") (pin "1") (pinfunction "1_1") (pintype "passive"))
      (node (ref "C39") (pin "2") (pinfunction "2_2") (pintype "passive"))
      (node (ref "C40") (pin "2") (pinfunction "2_2") (pintype "passive"))
      (node (ref "R51") (pin "2") (pinfunction "2_2") (pintype "passive"))
      (node (ref "R52") (pin "1") (pinfunction "1_1") (pintype "passive"))
      (node (ref "R63") (pin "1") (pinfunction "1_1") (pintype "passive"))
      (node (ref "T1") (pin "4") (pinfunction "GND_4") (pintype "power_in"))
      (node (ref "U2") (pin "4") (pinfunction "GND_4") (pintype "power_in"))
      (node (ref "U2") (pin "5") (pinfunction "GND_5") (pintype "power_in"))
      (node (ref "U2") (pin "9") (pinfunction "EP_9") (pintype "passive"))
    )
    (net (code "4") (name "-3_II") (class "Default")
      (node (ref "C24") (pin "1") (pinfunction "1_1") (pintype "passive"))
      (node (ref "C25") (pin "2") (pinfunction "2_2") (pintype "passive"))
      (node (ref "C37") (pin "2") (pinfunction "2_2") (pintype "passive"))
      (node (ref "C38") (pin "2") (pinfunction "2_2") (pintype "passive"))
      (node (ref "C43") (pin "2") (pinfunction "2_2") (pintype "passive"))
      (node (ref "C44") (pin "2") (pinfunction "2_2") (pintype "passive"))
      (node (ref "R11") (pin "1") (pinfunction "1_1") (pintype "passive"))
      (node (ref "R56") (pin "2") (pinfunction "2_2") (pintype "passive"))
      (node (ref "R57") (pin "1") (pinfunction "1_1") (pintype "passive"))
      (node (ref "T4") (pin "4") (pinfunction "GND_4") (pintype "power_in"))
      (node (ref "U3") (pin "4") (pinfunction "GND_4") (pintype "power_in"))
      (node (ref "U3") (pin "5") (pinfunction "GND_5") (pintype "power_in"))
      (node (ref "U3") (pin "9") (pinfunction "EP_9") (pintype "passive"))
    )
    (net (code "5") (name "/B_NTC") (class "Default")
      (node (ref "C32") (pin "1") (pinfunction "1_1") (pintype "passive"))
      (node (ref "DZ4") (pin "4") (pinfunction "ref_4") (pintype "passive"))
      (node (ref "J6") (pin "1") (pinfunction "1_1") (pintype "passive"))
      (node (ref "R36") (pin "1") (pinfunction "1_1") (pintype "passive"))
      (node (ref "R62") (pin "1") (pinfunction "1_1") (pintype "passive"))
      (node (ref "R67") (pin "2") (pinfunction "2_2") (pintype "passive"))
      (node (ref "R68") (pin "2") (pinfunction "2_2") (pintype "passive"))
    )
    (net (code "6") (name "/LED1") (class "Default")
      (node (ref "D3") (pin "1") (pinfunction "A_1") (pintype "passive"))
      (node (ref "R19") (pin "1") (pinfunction "1_1") (pintype "passive"))
      (node (ref "R23") (pin "1") (pinfunction "1_1") (pintype "passive"))
      (node (ref "R41") (pin "2") (pinfunction "2_2") (pintype "passive"))
      (node (ref "U4") (pin "8") (pinfunction "OUT3_8") (pintype "output"))
    )
    (net (code "7") (name "/LED2") (class "Default")
      (node (ref "D4") (pin "1") (pinfunction "A_1") (pintype "passive"))
      (node (ref "R20") (pin "1") (pinfunction "1_1") (pintype "passive"))
      (node (ref "R27") (pin "1") (pinfunction "1_1") (pintype "passive"))
      (node (ref "R43") (pin "2") (pinfunction "2_2") (pintype "passive"))
      (node (ref "U4") (pin "7") (pinfunction "OUT2_7") (pintype "output"))
    )
    (net (code "8") (name "/SIG1") (class "Default")
      (node (ref "R33") (pin "1") (pinfunction "1_1") (pintype "passive"))
      (node (ref "T5") (pin "6") (pinfunction "C_6") (pintype "passive"))
    )
    (net (code "9") (name "/SIG2") (class "Default")
      (node (ref "R34") (pin "1") (pinfunction "1_1") (pintype "passive"))
      (node (ref "T6") (pin "6") (pinfunction "C_6") (pintype "passive"))
    )
    (net (code "10") (name "/T_NTC") (class "Default")
      (node (ref "C28") (pin "1") (pinfunction "1_1") (pintype "passive"))
      (node (ref "DZ2") (pin "4") (pinfunction "ref_4") (pintype "passive"))
      (node (ref "J5") (pin "1") (pinfunction "1_1") (pintype "passive"))
      (node (ref "R18") (pin "1") (pinfunction "1_1") (pintype "passive"))
      (node (ref "R60") (pin "1") (pinfunction "1_1") (pintype "passive"))
      (node (ref "R64") (pin "1") (pinfunction "1_1") (pintype "passive"))
      (node (ref "R69") (pin "2") (pinfunction "2_2") (pintype "passive"))
    )
    (net (code "11") (name "400VDC") (class "Default")
      (node (ref "C1") (pin "1") (pinfunction "1_1") (pintype "passive"))
      (node (ref "C12") (pin "1") (pinfunction "1_1") (pintype "passive"))
      (node (ref "C13") (pin "1") (pinfunction "1_1") (pintype "passive"))
      (node (ref "C14") (pin "1") (pinfunction "1_1") (pintype "passive"))
      (node (ref "C5") (pin "1") (pinfunction "1_1") (pintype "passive"))
      (node (ref "C50") (pin "1") (pinfunction "1_1") (pintype "passive"))
      (node (ref "C6") (pin "1") (pinfunction "1_1") (pintype "passive"))
      (node (ref "J14") (pin "2") (pinfunction "2_2") (pintype "passive"))
      (node (ref "J3") (pin "1") (pinfunction "1_1") (pintype "passive"))
      (node (ref "J4") (pin "1") (pinfunction "1_1") (pintype "passive"))
      (node (ref "L2") (pin "1") (pinfunction "1_1") (pintype "passive"))
      (node (ref "L3") (pin "1") (pinfunction "1_1") (pintype "passive"))
      (node (ref "U5") (pin "2") (pinfunction "VAC_(L)_2") (pintype "power_in"))
    )
    (net (code "12") (name "400VDC_sens") (class "Default")
      (node (ref "C45") (pin "1") (pinfunction "1_1") (pintype "passive"))
      (node (ref "J14") (pin "1") (pinfunction "1_1") (pintype "passive"))
      (node (ref "R22") (pin "2") (pinfunction "2_2") (pintype "passive"))
    )
    (net (code "13") (name "GATE1") (class "Default")
      (node (ref "R4") (pin "2") (pinfunction "2_2") (pintype "passive"))
      (node (ref "R6") (pin "2") (pinfunction "2_2") (pintype "passive"))
      (node (ref "R7") (pin "2") (pinfunction "2_2") (pintype "passive"))
      (node (ref "T2") (pin "4") (pinfunction "G_4") (pintype "passive"))
    )
    (net (code "14") (name "GATE2") (class "Default")
      (node (ref "R10") (pin "2") (pinfunction "2_2") (pintype "passive"))
      (node (ref "R12") (pin "2") (pinfunction "2_2") (pintype "passive"))
      (node (ref "R13") (pin "2") (pinfunction "2_2") (pintype "passive"))
      (node (ref "T3") (pin "4") (pinfunction "G_4") (pintype "passive"))
    )
    (net (code "15") (name "GND") (class "Default")
      (node (ref "C1") (pin "2") (pinfunction "2_2") (pintype "passive"))
      (node (ref "C12") (pin "2") (pinfunction "2_2") (pintype "passive"))
      (node (ref "C13") (pin "2") (pinfunction "2_2") (pintype "passive"))
      (node (ref "C14") (pin "2") (pinfunction "2_2") (pintype "passive"))
      (node (ref "C33") (pin "2") (pinfunction "2_2") (pintype "passive"))
      (node (ref "C34") (pin "2") (pinfunction "2_2") (pintype "passive"))
      (node (ref "C5") (pin "2") (pinfunction "2_2") (pintype "passive"))
      (node (ref "C50") (pin "2") (pinfunction "2_2") (pintype "passive"))
      (node (ref "C6") (pin "2") (pinfunction "2_2") (pintype "passive"))
      (node (ref "L2") (pin "2") (pinfunction "2_2") (pintype "passive"))
      (node (ref "L3") (pin "2") (pinfunction "2_2") (pintype "passive"))
      (node (ref "RV1") (pin "2") (pinfunction "2_2") (pintype "passive"))
      (node (ref "RV2") (pin "2") (pinfunction "2_2") (pintype "passive"))
      (node (ref "T2") (pin "2") (pinfunction "S_2") (pintype "passive"))
      (node (ref "T3") (pin "2") (pinfunction "S_2") (pintype "passive"))
      (node (ref "U5") (pin "1") (pinfunction "VAC_(N)_1") (pintype "power_in"))
    )
    (net (code "16") (name "GND_SELV") (class "Default")
      (node (ref "C10") (pin "2") (pinfunction "2_2") (pintype "passive"))
      (node (ref "C17") (pin "1") (pinfunction "1_1") (pintype "passive"))
      (node (ref "C2") (pin "2") (pinfunction "-_2") (pintype "passive"))
      (node (ref "C28") (pin "2") (pinfunction "2_2") (pintype "passive"))
      (node (ref "C32") (pin "2") (pinfunction "2_2") (pintype "passive"))
      (node (ref "C35") (pin "2") (pinfunction "-_2") (pintype "passive"))
      (node (ref "C36") (pin "2") (pinfunction "2_2") (pintype "passive"))
      (node (ref "C4") (pin "2") (pinfunction "2_2") (pintype "passive"))
      (node (ref "C41") (pin "1") (pinfunction "1_1") (pintype "passive"))
      (node (ref "C8") (pin "2") (pinfunction "2_2") (pintype "passive"))
      (node (ref "D10") (pin "2") (pinfunction "K_2") (pintype "passive"))
      (node (ref "D11") (pin "2") (pinfunction "K_2") (pintype "passive"))
      (node (ref "DZ2") (pin "5") (pinfunction "A_5") (pintype "passive"))
      (node (ref "DZ4") (pin "5") (pinfunction "A_5") (pintype "passive"))
      (node (ref "DZ6") (pin "5") (pinfunction "A_5") (pintype "passive"))
      (node (ref "J12") (pin "3") (pinfunction "3_3") (pintype "passive"))
      (node (ref "J13") (pin "3") (pinfunction "3_3") (pintype "passive"))
      (node (ref "J5") (pin "2") (pinfunction "2_2") (pintype "passive"))
      (node (ref "J6") (pin "2") (pinfunction "2_2") (pintype "passive"))
      (node (ref "L1") (pin "3") (pinfunction "3_3") (pintype "passive"))
      (node (ref "R5") (pin "1") (pinfunction "1_1") (pintype "passive"))
      (node (ref "SW2") (pin "2") (pintype "passive"))
      (node (ref "SW2") (pin "5") (pintype "passive"))
      (node (ref "T12") (pin "2") (pinfunction "S_2") (pintype "passive"))
      (node (ref "T13") (pin "2") (pinfunction "S_2") (pintype "passive"))
      (node (ref "U1") (pin "2") (pinfunction "-VIN_2") (pintype "power_in"))
      (node (ref "U5") (pin "4") (pinfunction "-V_4") (pintype "output"))
      (node (ref "U6") (pin "2") (pinfunction "-VIN_2") (pintype "power_in"))
    )
    (net (code "17") (name "Net-(C3-Pad1)") (class "Default")
      (node (ref "C3") (pin "1") (pinfunction "1_1") (pintype "passive"))
      (node (ref "J2") (pin "1") (pinfunction "1_1") (pintype "passive"))
      (node (ref "L1") (pin "1") (pinfunction "1_1") (pintype "passive"))
    )
    (net (code "18") (name "Net-(C3-Pad2)") (class "Default")
      (node (ref "C3") (pin "2") (pinfunction "2_2") (pintype "passive"))
      (node (ref "J2") (pin "2") (pinfunction "2_2") (pintype "passive"))
      (node (ref "L1") (pin "2") (pinfunction "2_2") (pintype "passive"))
    )
    (net (code "19") (name "Net-(C33-Pad1)") (class "Default")
      (node (ref "C33") (pin "1") (pinfunction "1_1") (pintype "passive"))
      (node (ref "R38") (pin "1") (pinfunction "1_1") (pintype "passive"))
    )
    (net (code "20") (name "Net-(C34-Pad1)") (class "Default")
      (node (ref "C34") (pin "1") (pinfunction "1_1") (pintype "passive"))
      (node (ref "R39") (pin "1") (pinfunction "1_1") (pintype "passive"))
    )
    (net (code "21") (name "Net-(C45-Pad2)") (class "Default")
      (node (ref "C45") (pin "2") (pinfunction "2_2") (pintype "passive"))
      (node (ref "C46") (pin "1") (pinfunction "1_1") (pintype "passive"))
      (node (ref "R21") (pin "2") (pinfunction "2_2") (pintype "passive"))
      (node (ref "R22") (pin "1") (pinfunction "1_1") (pintype "passive"))
    )
    (net (code "22") (name "Net-(C46-Pad2)") (class "Default")
      (node (ref "C46") (pin "2") (pinfunction "2_2") (pintype "passive"))
      (node (ref "C47") (pin "1") (pinfunction "1_1") (pintype "passive"))
      (node (ref "R21") (pin "1") (pinfunction "1_1") (pintype "passive"))
      (node (ref "R24") (pin "2") (pinfunction "2_2") (pintype "passive"))
    )
    (net (code "23") (name "Net-(C47-Pad2)") (class "Default")
      (node (ref "C47") (pin "2") (pinfunction "2_2") (pintype "passive"))
      (node (ref "RT1") (pin "1") (pinfunction "1_1") (pintype "passive"))
      (node (ref "SW1") (pin "1") (pintype "passive"))
      (node (ref "SW1") (pin "3") (pintype "passive"))
    )
    (net (code "24") (name "Net-(C49-Pad1)") (class "Default")
      (node (ref "C49") (pin "1") (pinfunction "1_1") (pintype "passive"))
      (node (ref "C7") (pin "2") (pinfunction "2_2") (pintype "passive"))
      (node (ref "J9") (pin "1") (pinfunction "1_1") (pintype "passive"))
      (node (ref "J9") (pin "2") (pinfunction "2_2") (pintype "passive"))
      (node (ref "L2") (pin "3") (pinfunction "3_3") (pintype "passive"))
      (node (ref "L3") (pin "3") (pinfunction "3_3") (pintype "passive"))
    )
    (net (code "25") (name "Net-(C49-Pad2)") (class "Default")
      (node (ref "C49") (pin "2") (pinfunction "2_2") (pintype "passive"))
      (node (ref "C7") (pin "1") (pinfunction "1_1") (pintype "passive"))
      (node (ref "J1") (pin "1") (pinfunction "1_1") (pintype "passive"))
      (node (ref "J1") (pin "2") (pinfunction "2_2") (pintype "passive"))
      (node (ref "L2") (pin "4") (pinfunction "4_4") (pintype "passive"))
      (node (ref "L3") (pin "4") (pinfunction "4_4") (pintype "passive"))
    )
    (net (code "26") (name "Net-(D1-A)") (class "Default")
      (node (ref "C4") (pin "1") (pinfunction "1_1") (pintype "passive"))
      (node (ref "D1") (pin "1") (pinfunction "A_1") (pintype "passive"))
      (node (ref "L1") (pin "4") (pinfunction "4_4") (pintype "passive"))
    )
    (net (code "27") (name "Net-(D2-A)") (class "Default")
      (node (ref "D2") (pin "1") (pinfunction "A_1") (pintype "passive"))
      (node (ref "R4") (pin "1") (pinfunction "1_1") (pintype "passive"))
    )
    (net (code "28") (name "Net-(D2-K)") (class "Default")
      (node (ref "D2") (pin "2") (pinfunction "K_2") (pintype "passive"))
      (node (ref "R7") (pin "1") (pinfunction "1_1") (pintype "passive"))
      (node (ref "U2") (pin "6") (pinfunction "OUTL_6") (pintype "open_collector"))
      (node (ref "U2") (pin "7") (pinfunction "OUTH_7") (pintype "output"))
    )
    (net (code "29") (name "Net-(D3-K)") (class "Default")
      (node (ref "D3") (pin "2") (pinfunction "K_2") (pintype "passive"))
      (node (ref "R3") (pin "2") (pinfunction "2_2") (pintype "passive"))
    )
    (net (code "30") (name "Net-(D4-K)") (class "Default")
      (node (ref "D4") (pin "2") (pinfunction "K_2") (pintype "passive"))
      (node (ref "R14") (pin "2") (pinfunction "2_2") (pintype "passive"))
    )
    (net (code "31") (name "Net-(D5-A)") (class "Default")
      (node (ref "D5") (pin "1") (pinfunction "A_1") (pintype "passive"))
      (node (ref "R13") (pin "1") (pinfunction "1_1") (pintype "passive"))
    )
    (net (code "32") (name "Net-(D5-K)") (class "Default")
      (node (ref "D5") (pin "2") (pinfunction "K_2") (pintype "passive"))
      (node (ref "R10") (pin "1") (pinfunction "1_1") (pintype "passive"))
      (node (ref "U3") (pin "6") (pinfunction "OUTL_6") (pintype "open_collector"))
      (node (ref "U3") (pin "7") (pinfunction "OUTH_7") (pintype "output"))
    )
    (net (code "33") (name "Net-(D6-A)") (class "Default")
      (node (ref "D6") (pin "1") (pinfunction "A_1") (pintype "passive"))
      (node (ref "D7") (pin "1") (pinfunction "A_1") (pintype "passive"))
      (node (ref "R19") (pin "2") (pinfunction "2_2") (pintype "passive"))
    )
    (net (code "34") (name "Net-(D8-A)") (class "Default")
      (node (ref "D8") (pin "1") (pinfunction "A_1") (pintype "passive"))
      (node (ref "D9") (pin "1") (pinfunction "A_1") (pintype "passive"))
      (node (ref "R20") (pin "2") (pinfunction "2_2") (pintype "passive"))
    )
    (net (code "35") (name "Net-(D10-A)") (class "Default")
      (node (ref "D10") (pin "1") (pinfunction "A_1") (pintype "passive"))
      (node (ref "D11") (pin "1") (pinfunction "A_1") (pintype "passive"))
      (node (ref "R40") (pin "2") (pinfunction "2_2") (pintype "passive"))
    )
    (net (code "36") (name "Net-(D12-A)") (class "Default")
      (node (ref "D12") (pin "1") (pinfunction "A_1") (pintype "passive"))
      (node (ref "J7") (pin "2") (pinfunction "2_2") (pintype "passive"))
      (node (ref "T7") (pin "4") (pinfunction "E_4") (pintype "passive"))
    )
    (net (code "37") (name "Net-(D12-K)") (class "Default")
      (node (ref "D12") (pin "2") (pinfunction "K_2") (pintype "passive"))
      (node (ref "J7") (pin "1") (pinfunction "1_1") (pintype "passive"))
      (node (ref "T7") (pin "6") (pinfunction "C_6") (pintype "passive"))
    )
    (net (code "38") (name "Net-(D13-A)") (class "Default")
      (node (ref "D13") (pin "1") (pinfunction "A_1") (pintype "passive"))
      (node (ref "J8") (pin "2") (pinfunction "2_2") (pintype "passive"))
      (node (ref "T8") (pin "4") (pinfunction "E_4") (pintype "passive"))
    )
    (net (code "39") (name "Net-(D13-K)") (class "Default")
      (node (ref "D13") (pin "2") (pinfunction "K_2") (pintype "passive"))
      (node (ref "J8") (pin "1") (pinfunction "1_1") (pintype "passive"))
      (node (ref "T8") (pin "6") (pinfunction "C_6") (pintype "passive"))
    )
    (net (code "40") (name "Net-(D14-A)") (class "Default")
      (node (ref "D14") (pin "1") (pinfunction "A_1") (pintype "passive"))
      (node (ref "J10") (pin "2") (pinfunction "2_2") (pintype "passive"))
      (node (ref "T9") (pin "4") (pinfunction "E_4") (pintype "passive"))
    )
    (net (code "41") (name "Net-(D14-K)") (class "Default")
      (node (ref "D14") (pin "2") (pinfunction "K_2") (pintype "passive"))
      (node (ref "J10") (pin "1") (pinfunction "1_1") (pintype "passive"))
      (node (ref "T9") (pin "6") (pinfunction "C_6") (pintype "passive"))
    )
    (net (code "42") (name "Net-(D15-A)") (class "Default")
      (node (ref "D15") (pin "1") (pinfunction "A_1") (pintype "passive"))
      (node (ref "J11") (pin "2") (pinfunction "2_2") (pintype "passive"))
      (node (ref "T10") (pin "4") (pinfunction "E_4") (pintype "passive"))
    )
    (net (code "43") (name "Net-(D15-K)") (class "Default")
      (node (ref "D15") (pin "2") (pinfunction "K_2") (pintype "passive"))
      (node (ref "J11") (pin "1") (pinfunction "1_1") (pintype "passive"))
      (node (ref "T10") (pin "6") (pinfunction "C_6") (pintype "passive"))
    )
    (net (code "44") (name "Net-(DZ1-A)") (class "Default")
      (node (ref "DZ1") (pin "1") (pinfunction "A_1") (pintype "passive"))
      (node (ref "R50") (pin "2") (pinfunction "2_2") (pintype "passive"))
      (node (ref "R51") (pin "1") (pinfunction "1_1") (pintype "passive"))
    )
    (net (code "45") (name "Net-(DZ1-K)") (class "Default")
      (node (ref "C18") (pin "1") (pinfunction "1_1") (pintype "passive"))
      (node (ref "C9") (pin "2") (pinfunction "2_2") (pintype "passive"))
      (node (ref "DZ1") (pin "2") (pinfunction "K_2") (pintype "passive"))
      (node (ref "R1") (pin "1") (pinfunction "1_1") (pintype "passive"))
      (node (ref "R2") (pin "2") (pinfunction "2_2") (pintype "passive"))
      (node (ref "R49") (pin "1") (pinfunction "1_1") (pintype "passive"))
    )
    (net (code "46") (name "Net-(DZ2-K)") (class "Default")
      (node (ref "DZ2") (pin "3") (pinfunction "K_3") (pintype "passive"))
      (node (ref "R17") (pin "1") (pinfunction "1_1") (pintype "passive"))
      (node (ref "R46") (pin "2") (pinfunction "2_2") (pintype "passive"))
      (node (ref "R60") (pin "2") (pinfunction "2_2") (pintype "passive"))
      (node (ref "R65") (pin "1") (pinfunction "1_1") (pintype "passive"))
      (node (ref "T5") (pin "3") (pinfunction "K_3") (pintype "passive"))
    )
    (net (code "47") (name "Net-(DZ3-K)") (class "Default")
      (node (ref "C31") (pin "1") (pinfunction "1_1") (pintype "passive"))
      (node (ref "DZ3") (pin "3") (pinfunction "K_3") (pintype "passive"))
      (node (ref "R28") (pin "2") (pinfunction "2_2") (pintype "passive"))
      (node (ref "R29") (pin "2") (pinfunction "2_2") (pintype "passive"))
      (node (ref "R31") (pin "2") (pinfunction "2_2") (pintype "passive"))
      (node (ref "RT2") (pin "1") (pinfunction "1_1") (pintype "passive"))
      (node (ref "U4") (pin "12") (pinfunction "IN4+_12") (pintype "input"))
    )
    (net (code "48") (name "Net-(DZ3-ref)") (class "Default")
      (node (ref "DZ3") (pin "4") (pinfunction "ref_4") (pintype "passive"))
      (node (ref "R31") (pin "1") (pinfunction "1_1") (pintype "passive"))
      (node (ref "R32") (pin "1") (pinfunction "1_1") (pintype "passive"))
      (node (ref "R37") (pin "2") (pinfunction "2_2") (pintype "passive"))
    )
    (net (code "49") (name "Net-(DZ4-K)") (class "Default")
      (node (ref "DZ4") (pin "3") (pinfunction "K_3") (pintype "passive"))
      (node (ref "R35") (pin "1") (pinfunction "1_1") (pintype "passive"))
      (node (ref "R48") (pin "2") (pinfunction "2_2") (pintype "passive"))
      (node (ref "R62") (pin "2") (pinfunction "2_2") (pintype "passive"))
      (node (ref "R66") (pin "2") (pinfunction "2_2") (pintype "passive"))
      (node (ref "T6") (pin "3") (pinfunction "K_3") (pintype "passive"))
    )
    (net (code "50") (name "Net-(DZ5-A)") (class "Default")
      (node (ref "DZ5") (pin "1") (pinfunction "A_1") (pintype "passive"))
      (node (ref "R55") (pin "2") (pinfunction "2_2") (pintype "passive"))
      (node (ref "R56") (pin "1") (pinfunction "1_1") (pintype "passive"))
    )
    (net (code "51") (name "Net-(DZ5-K)") (class "Default")
      (node (ref "C22") (pin "2") (pinfunction "2_2") (pintype "passive"))
      (node (ref "C44") (pin "1") (pinfunction "1_1") (pintype "passive"))
      (node (ref "DZ5") (pin "2") (pinfunction "K_2") (pintype "passive"))
      (node (ref "R53") (pin "2") (pinfunction "2_2") (pintype "passive"))
      (node (ref "R54") (pin "1") (pinfunction "1_1") (pintype "passive"))
      (node (ref "R9") (pin "1") (pinfunction "1_1") (pintype "passive"))
    )
    (net (code "52") (name "Net-(DZ6-K)") (class "Default")
      (node (ref "DZ6") (pin "3") (pinfunction "K_3") (pintype "passive"))
      (node (ref "R58") (pin "2") (pinfunction "2_2") (pintype "passive"))
      (node (ref "T11") (pin "2") (pinfunction "G2_2") (pintype "passive"))
      (node (ref "T11") (pin "4") (pinfunction "G2_4") (pintype "passive"))
    )
    (net (code "53") (name "Net-(DZ6-ref)") (class "Default")
      (node (ref "DZ6") (pin "4") (pinfunction "ref_4") (pintype "passive"))
      (node (ref "R5") (pin "2") (pinfunction "2_2") (pintype "passive"))
      (node (ref "R59") (pin "1") (pinfunction "1_1") (pintype "passive"))
      (node (ref "RT3") (pin "1") (pinfunction "1_1") (pintype "passive"))
    )
    (net (code "54") (name "Net-(R24-Pad1)") (class "Default")
      (node (ref "R24") (pin "1") (pinfunction "1_1") (pintype "passive"))
      (node (ref "RT1") (pin "2") (pinfunction "2_2") (pintype "passive"))
    )
    (net (code "55") (name "Net-(R28-Pad1)") (class "Default")
      (node (ref "R28") (pin "1") (pinfunction "1_1") (pintype "passive"))
      (node (ref "R32") (pin "2") (pinfunction "2_2") (pintype "passive"))
      (node (ref "RT2") (pin "2") (pinfunction "2_2") (pintype "passive"))
    )
    (net (code "56") (name "Net-(R68-Pad1)") (class "Default")
      (node (ref "R68") (pin "1") (pinfunction "1_1") (pintype "passive"))
      (node (ref "SW2") (pin "1") (pintype "passive"))
    )
    (net (code "57") (name "Net-(R69-Pad1)") (class "Default")
      (node (ref "R69") (pin "1") (pinfunction "1_1") (pintype "passive"))
      (node (ref "SW2") (pin "4") (pintype "passive"))
    )
    (net (code "58") (name "Net-(T1-A)") (class "Default")
      (node (ref "C19") (pin "1") (pinfunction "1_1") (pintype "passive"))
      (node (ref "R3") (pin "1") (pinfunction "1_1") (pintype "passive"))
      (node (ref "T1") (pin "1") (pinfunction "A_1") (pintype "passive"))
    )
    (net (code "59") (name "Net-(T1-OUT)") (class "Default")
      (node (ref "R63") (pin "2") (pinfunction "2_2") (pintype "passive"))
      (node (ref "T1") (pin "5") (pinfunction "OUT_5") (pintype "output"))
      (node (ref "U2") (pin "2") (pinfunction "IN_2") (pintype "input"))
    )
    (net (code "60") (name "Net-(T2-D)") (class "Default")
      (node (ref "J3") (pin "2") (pinfunction "2_2") (pintype "passive"))
      (node (ref "R38") (pin "2") (pinfunction "2_2") (pintype "passive"))
      (node (ref "RV1") (pin "1") (pinfunction "1_1") (pintype "passive"))
      (node (ref "T2") (pin "1") (pinfunction "D_1") (pintype "passive"))
    )
    (net (code "61") (name "Net-(T3-D)") (class "Default")
      (node (ref "J4") (pin "2") (pinfunction "2_2") (pintype "passive"))
      (node (ref "R39") (pin "2") (pinfunction "2_2") (pintype "passive"))
      (node (ref "RV2") (pin "1") (pinfunction "1_1") (pintype "passive"))
      (node (ref "T3") (pin "1") (pinfunction "D_1") (pintype "passive"))
    )
    (net (code "62") (name "Net-(T4-A)") (class "Default")
      (node (ref "C26") (pin "1") (pinfunction "1_1") (pintype "passive"))
      (node (ref "R14") (pin "1") (pinfunction "1_1") (pintype "passive"))
      (node (ref "T4") (pin "1") (pinfunction "A_1") (pintype "passive"))
    )
    (net (code "63") (name "Net-(T4-OUT)") (class "Default")
      (node (ref "R11") (pin "2") (pinfunction "2_2") (pintype "passive"))
      (node (ref "T4") (pin "5") (pinfunction "OUT_5") (pintype "output"))
      (node (ref "U3") (pin "2") (pinfunction "IN_2") (pintype "input"))
    )
    (net (code "64") (name "Net-(T5-A)") (class "Default")
      (node (ref "R15") (pin "1") (pinfunction "1_1") (pintype "passive"))
      (node (ref "R17") (pin "2") (pinfunction "2_2") (pintype "passive"))
      (node (ref "T5") (pin "1") (pinfunction "A_1") (pintype "passive"))
    )
    (net (code "65") (name "Net-(T6-A)") (class "Default")
      (node (ref "R30") (pin "1") (pinfunction "1_1") (pintype "passive"))
      (node (ref "R35") (pin "2") (pinfunction "2_2") (pintype "passive"))
      (node (ref "T6") (pin "1") (pinfunction "A_1") (pintype "passive"))
    )
    (net (code "66") (name "Net-(T7-A)") (class "Default")
      (node (ref "R41") (pin "1") (pinfunction "1_1") (pintype "passive"))
      (node (ref "R42") (pin "2") (pinfunction "2_2") (pintype "passive"))
      (node (ref "T7") (pin "1") (pinfunction "A_1") (pintype "passive"))
    )
    (net (code "67") (name "Net-(T8-A)") (class "Default")
      (node (ref "R43") (pin "1") (pinfunction "1_1") (pintype "passive"))
      (node (ref "R44") (pin "2") (pinfunction "2_2") (pintype "passive"))
      (node (ref "T8") (pin "1") (pinfunction "A_1") (pintype "passive"))
    )
    (net (code "68") (name "Net-(T9-K)") (class "Default")
      (node (ref "R45") (pin "2") (pinfunction "2_2") (pintype "passive"))
      (node (ref "R46") (pin "1") (pinfunction "1_1") (pintype "passive"))
      (node (ref "T9") (pin "3") (pinfunction "K_3") (pintype "passive"))
    )
    (net (code "69") (name "Net-(T10-K)") (class "Default")
      (node (ref "R47") (pin "2") (pinfunction "2_2") (pintype "passive"))
      (node (ref "R48") (pin "1") (pinfunction "1_1") (pintype "passive"))
      (node (ref "T10") (pin "3") (pinfunction "K_3") (pintype "passive"))
    )
    (net (code "70") (name "Net-(T11B-D21)") (class "Default")
      (node (ref "J13") (pin "1") (pinfunction "1_1") (pintype "passive"))
      (node (ref "R59") (pin "2") (pinfunction "2_2") (pintype "passive"))
      (node (ref "T11") (pin "5") (pinfunction "D21_5") (pintype "passive"))
      (node (ref "T11") (pin "6") (pinfunction "D22_6") (pintype "passive"))
      (node (ref "T11") (pin "7") (pinfunction "D1_7") (pintype "passive"))
      (node (ref "T11") (pin "8") (pinfunction "D1_8") (pintype "passive"))
    )
    (net (code "71") (name "Net-(T12-D)") (class "Default")
      (node (ref "R64") (pin "2") (pinfunction "2_2") (pintype "passive"))
      (node (ref "T12") (pin "3") (pinfunction "D_3") (pintype "passive"))
    )
    (net (code "72") (name "Net-(T12-G)") (class "Default")
      (node (ref "R65") (pin "2") (pinfunction "2_2") (pintype "passive"))
      (node (ref "T12") (pin "1") (pinfunction "G_1") (pintype "passive"))
    )
    (net (code "73") (name "Net-(T13-D)") (class "Default")
      (node (ref "R67") (pin "1") (pinfunction "1_1") (pintype "passive"))
      (node (ref "T13") (pin "3") (pinfunction "D_3") (pintype "passive"))
    )
    (net (code "74") (name "Net-(T13-G)") (class "Default")
      (node (ref "R66") (pin "1") (pinfunction "1_1") (pintype "passive"))
      (node (ref "T13") (pin "1") (pinfunction "G_1") (pintype "passive"))
    )
    (net (code "75") (name "Net-(U1--V)") (class "Default")
      (node (ref "C16") (pin "2") (pinfunction "2_2") (pintype "passive"))
      (node (ref "C17") (pin "2") (pinfunction "2_2") (pintype "passive"))
      (node (ref "R50") (pin "1") (pinfunction "1_1") (pintype "passive"))
      (node (ref "U1") (pin "5") (pinfunction "-V_5") (pintype "output"))
    )
    (net (code "76") (name "Net-(U1-CMM)") (class "Default")
      (node (ref "C11") (pin "2") (pinfunction "2_2") (pintype "passive"))
      (node (ref "C16") (pin "1") (pinfunction "1_1") (pintype "passive"))
      (node (ref "R2") (pin "1") (pinfunction "1_1") (pintype "passive"))
      (node (ref "U1") (pin "6") (pinfunction "CMM_6") (pintype "passive"))
    )
    (net (code "77") (name "Net-(U4A-IN1+)") (class "Default")
      (node (ref "C48") (pin "1") (pinfunction "1_1") (pintype "passive"))
      (node (ref "R26") (pin "2") (pinfunction "2_2") (pintype "passive"))
      (node (ref "SW1") (pin "2") (pintype "passive"))
      (node (ref "U4") (pin "3") (pinfunction "IN1+_3") (pintype "input"))
    )
    (net (code "78") (name "Net-(U4A-IN1-)") (class "Default")
      (node (ref "R16") (pin "1") (pinfunction "1_1") (pintype "passive"))
      (node (ref "R25") (pin "1") (pinfunction "1_1") (pintype "passive"))
      (node (ref "U4") (pin "1") (pinfunction "OUT1_1") (pintype "output"))
      (node (ref "U4") (pin "2") (pinfunction "IN1-_2") (pintype "input"))
    )
    (net (code "79") (name "Net-(U4B-IN2+)") (class "Default")
      (node (ref "R25") (pin "2") (pinfunction "2_2") (pintype "passive"))
      (node (ref "R27") (pin "2") (pinfunction "2_2") (pintype "passive"))
      (node (ref "U4") (pin "5") (pinfunction "IN2+_5") (pintype "input"))
    )
    (net (code "80") (name "Net-(U4C-IN3+)") (class "Default")
      (node (ref "R16") (pin "2") (pinfunction "2_2") (pintype "passive"))
      (node (ref "R23") (pin "2") (pinfunction "2_2") (pintype "passive"))
      (node (ref "U4") (pin "10") (pinfunction "IN3+_10") (pintype "input"))
    )
    (net (code "81") (name "Net-(U6--V)") (class "Default")
      (node (ref "C41") (pin "2") (pinfunction "2_2") (pintype "passive"))
      (node (ref "C42") (pin "2") (pinfunction "2_2") (pintype "passive"))
      (node (ref "R55") (pin "1") (pinfunction "1_1") (pintype "passive"))
      (node (ref "U6") (pin "5") (pinfunction "-V_5") (pintype "output"))
    )
    (net (code "82") (name "Net-(U6-CMM)") (class "Default")
      (node (ref "C23") (pin "2") (pinfunction "2_2") (pintype "passive"))
      (node (ref "C42") (pin "1") (pinfunction "1_1") (pintype "passive"))
      (node (ref "R53") (pin "1") (pinfunction "1_1") (pintype "passive"))
      (node (ref "U6") (pin "6") (pinfunction "CMM_6") (pintype "passive"))
    )
    (net (code "83") (name "REF1") (class "Default")
      (node (ref "B1") (pin "2") (pinfunction "B0_2") (pintype "passive"))
      (node (ref "B1") (pin "3") (pinfunction "B1_3") (pintype "passive"))
      (node (ref "B3") (pin "2") (pinfunction "B0_2") (pintype "passive"))
      (node (ref "C27") (pin "2") (pinfunction "2_2") (pintype "passive"))
      (node (ref "R33") (pin "2") (pinfunction "2_2") (pintype "passive"))
      (node (ref "U4") (pin "9") (pinfunction "IN3-_9") (pintype "input"))
    )
    (net (code "84") (name "REF2") (class "Default")
      (node (ref "B2") (pin "2") (pinfunction "B0_2") (pintype "passive"))
      (node (ref "B2") (pin "3") (pinfunction "B1_3") (pintype "passive"))
      (node (ref "B4") (pin "2") (pinfunction "B0_2") (pintype "passive"))
      (node (ref "C29") (pin "2") (pinfunction "2_2") (pintype "passive"))
      (node (ref "R34") (pin "2") (pinfunction "2_2") (pintype "passive"))
      (node (ref "U4") (pin "6") (pinfunction "IN2-_6") (pintype "input"))
    )
    (net (code "85") (name "SH") (class "Default")
      (node (ref "B3") (pin "0") (pinfunction "SH_0") (pintype "passive"))
      (node (ref "B4") (pin "0") (pinfunction "SH_0") (pintype "passive"))
      (node (ref "R61") (pin "1") (pinfunction "1_1") (pintype "passive"))
      (node (ref "SW1") (pin "0") (pintype "passive"))
    )
    (net (code "86") (name "SOURCE1") (class "Default")
      (node (ref "B1") (pin "1") (pinfunction "A0_1") (pintype "passive"))
      (node (ref "B1") (pin "4") (pinfunction "A1_4") (pintype "passive"))
      (node (ref "B2") (pin "1") (pinfunction "A0_1") (pintype "passive"))
      (node (ref "B2") (pin "4") (pinfunction "A1_4") (pintype "passive"))
      (node (ref "B3") (pin "1") (pinfunction "A0_1") (pintype "passive"))
      (node (ref "B4") (pin "1") (pinfunction "A0_1") (pintype "passive"))
      (node (ref "C19") (pin "2") (pinfunction "2_2") (pintype "passive"))
      (node (ref "C20") (pin "1") (pinfunction "1_1") (pintype "passive"))
      (node (ref "C21") (pin "2") (pinfunction "2_2") (pintype "passive"))
      (node (ref "C26") (pin "2") (pinfunction "2_2") (pintype "passive"))
      (node (ref "C27") (pin "1") (pinfunction "1_1") (pintype "passive"))
      (node (ref "C29") (pin "1") (pinfunction "1_1") (pintype "passive"))
      (node (ref "C30") (pin "2") (pinfunction "2_2") (pintype "passive"))
      (node (ref "C31") (pin "2") (pinfunction "2_2") (pintype "passive"))
      (node (ref "C48") (pin "2") (pinfunction "2_2") (pintype "passive"))
      (node (ref "D6") (pin "2") (pinfunction "K_2") (pintype "passive"))
      (node (ref "D7") (pin "2") (pinfunction "K_2") (pintype "passive"))
      (node (ref "D8") (pin "2") (pinfunction "K_2") (pintype "passive"))
      (node (ref "D9") (pin "2") (pinfunction "K_2") (pintype "passive"))
      (node (ref "DZ3") (pin "5") (pinfunction "A_5") (pintype "passive"))
      (node (ref "R26") (pin "1") (pinfunction "1_1") (pintype "passive"))
      (node (ref "R37") (pin "1") (pinfunction "1_1") (pintype "passive"))
      (node (ref "R42") (pin "1") (pinfunction "1_1") (pintype "passive"))
      (node (ref "R44") (pin "1") (pinfunction "1_1") (pintype "passive"))
      (node (ref "R49") (pin "2") (pinfunction "2_2") (pintype "passive"))
      (node (ref "R52") (pin "2") (pinfunction "2_2") (pintype "passive"))
      (node (ref "R6") (pin "1") (pinfunction "1_1") (pintype "passive"))
      (node (ref "R61") (pin "2") (pinfunction "2_2") (pintype "passive"))
      (node (ref "R8") (pin "1") (pinfunction "1_1") (pintype "passive"))
      (node (ref "T1") (pin "3") (pinfunction "K_3") (pintype "passive"))
      (node (ref "T2") (pin "3") (pinfunction "S_3") (pintype "passive"))
      (node (ref "T4") (pin "3") (pinfunction "K_3") (pintype "passive"))
      (node (ref "T5") (pin "4") (pinfunction "E_4") (pintype "passive"))
      (node (ref "T6") (pin "4") (pinfunction "E_4") (pintype "passive"))
      (node (ref "T7") (pin "3") (pinfunction "K_3") (pintype "passive"))
      (node (ref "T8") (pin "3") (pinfunction "K_3") (pintype "passive"))
      (node (ref "U4") (pin "11") (pinfunction "V-_11") (pintype "power_in"))
    )
    (net (code "87") (name "SOURCE2") (class "Default")
      (node (ref "C24") (pin "2") (pinfunction "2_2") (pintype "passive"))
      (node (ref "C25") (pin "1") (pinfunction "1_1") (pintype "passive"))
      (node (ref "R12") (pin "1") (pinfunction "1_1") (pintype "passive"))
      (node (ref "R54") (pin "2") (pinfunction "2_2") (pintype "passive"))
      (node (ref "R57") (pin "2") (pinfunction "2_2") (pintype "passive"))
      (node (ref "R8") (pin "2") (pinfunction "2_2") (pintype "passive"))
      (node (ref "T3") (pin "3") (pinfunction "S_3") (pintype "passive"))
    )
    (net (code "88") (name "VCC_12") (class "Default")
      (node (ref "C10") (pin "1") (pinfunction "1_1") (pintype "passive"))
      (node (ref "C2") (pin "1") (pinfunction "+_1") (pintype "passive"))
      (node (ref "C35") (pin "1") (pinfunction "+_1") (pintype "passive"))
      (node (ref "C36") (pin "1") (pinfunction "1_1") (pintype "passive"))
      (node (ref "C8") (pin "1") (pinfunction "1_1") (pintype "passive"))
      (node (ref "D1") (pin "2") (pinfunction "K_2") (pintype "passive"))
      (node (ref "J12") (pin "1") (pinfunction "1_1") (pintype "passive"))
      (node (ref "R15") (pin "2") (pinfunction "2_2") (pintype "passive"))
      (node (ref "R18") (pin "2") (pinfunction "2_2") (pintype "passive"))
      (node (ref "R30") (pin "2") (pinfunction "2_2") (pintype "passive"))
      (node (ref "R36") (pin "2") (pinfunction "2_2") (pintype "passive"))
      (node (ref "R40") (pin "1") (pinfunction "1_1") (pintype "passive"))
      (node (ref "R45") (pin "1") (pinfunction "1_1") (pintype "passive"))
      (node (ref "R47") (pin "1") (pinfunction "1_1") (pintype "passive"))
      (node (ref "R58") (pin "1") (pinfunction "1_1") (pintype "passive"))
      (node (ref "RT3") (pin "2") (pinfunction "2_2") (pintype "passive"))
      (node (ref "T10") (pin "1") (pinfunction "A_1") (pintype "passive"))
      (node (ref "T11") (pin "1") (pinfunction "S1_1") (pintype "passive"))
      (node (ref "T11") (pin "3") (pinfunction "S2_3") (pintype "passive"))
      (node (ref "T9") (pin "1") (pinfunction "A_1") (pintype "passive"))
      (node (ref "U1") (pin "1") (pinfunction "+VIN_1") (pintype "power_in"))
      (node (ref "U5") (pin "5") (pinfunction "+V_5") (pintype "output"))
      (node (ref "U6") (pin "1") (pinfunction "+VIN_1") (pintype "power_in"))
    )
    (net (code "89") (name "VREF") (class "Default")
      (node (ref "R33") (pin "3") (pinfunction "3_3") (pintype "passive"))
      (node (ref "R34") (pin "3") (pinfunction "3_3") (pintype "passive"))
      (node (ref "U4") (pin "13") (pinfunction "IN4-_13") (pintype "input"))
      (node (ref "U4") (pin "14") (pinfunction "OUT4_14") (pintype "output"))
    )
    (net (code "90") (name "unconnected-(J12-Pad2)") (class "Default")
      (node (ref "J12") (pin "2") (pinfunction "2_2") (pintype "passive"))
    )
    (net (code "91") (name "unconnected-(J13-Pad2)") (class "Default")
      (node (ref "J13") (pin "2") (pinfunction "2_2") (pintype "passive"))
    )
    (net (code "92") (name "unconnected-(SW2-Pad0)") (class "Default")
      (node (ref "SW2") (pin "0") (pintype "passive"))
    )
    (net (code "93") (name "unconnected-(SW2-Pad3)") (class "Default")
      (node (ref "SW2") (pin "3") (pintype "passive"))
    )
    (net (code "94") (name "unconnected-(SW2-Pad6)") (class "Default")
      (node (ref "SW2") (pin "6") (pintype "passive"))
    )
    (net (code "95") (name "unconnected-(U2-nc-Pad3)") (class "Default")
      (node (ref "U2") (pin "3") (pinfunction "nc_3") (pintype "passive"))
    )
    (net (code "96") (name "unconnected-(U3-nc-Pad3)") (class "Default")
      (node (ref "U3") (pin "3") (pinfunction "nc_3") (pintype "passive"))
    )
    (net (code "97") (name "unconnected-(U5-nc-Pad3)") (class "Default")
      (node (ref "U5") (pin "3") (pinfunction "nc_3") (pintype "passive"))
    )
  )
)
